# HDMI_RGB_LVDS_fertig_V3.net
KiCad netlist of a schematic drawn in EAGLE
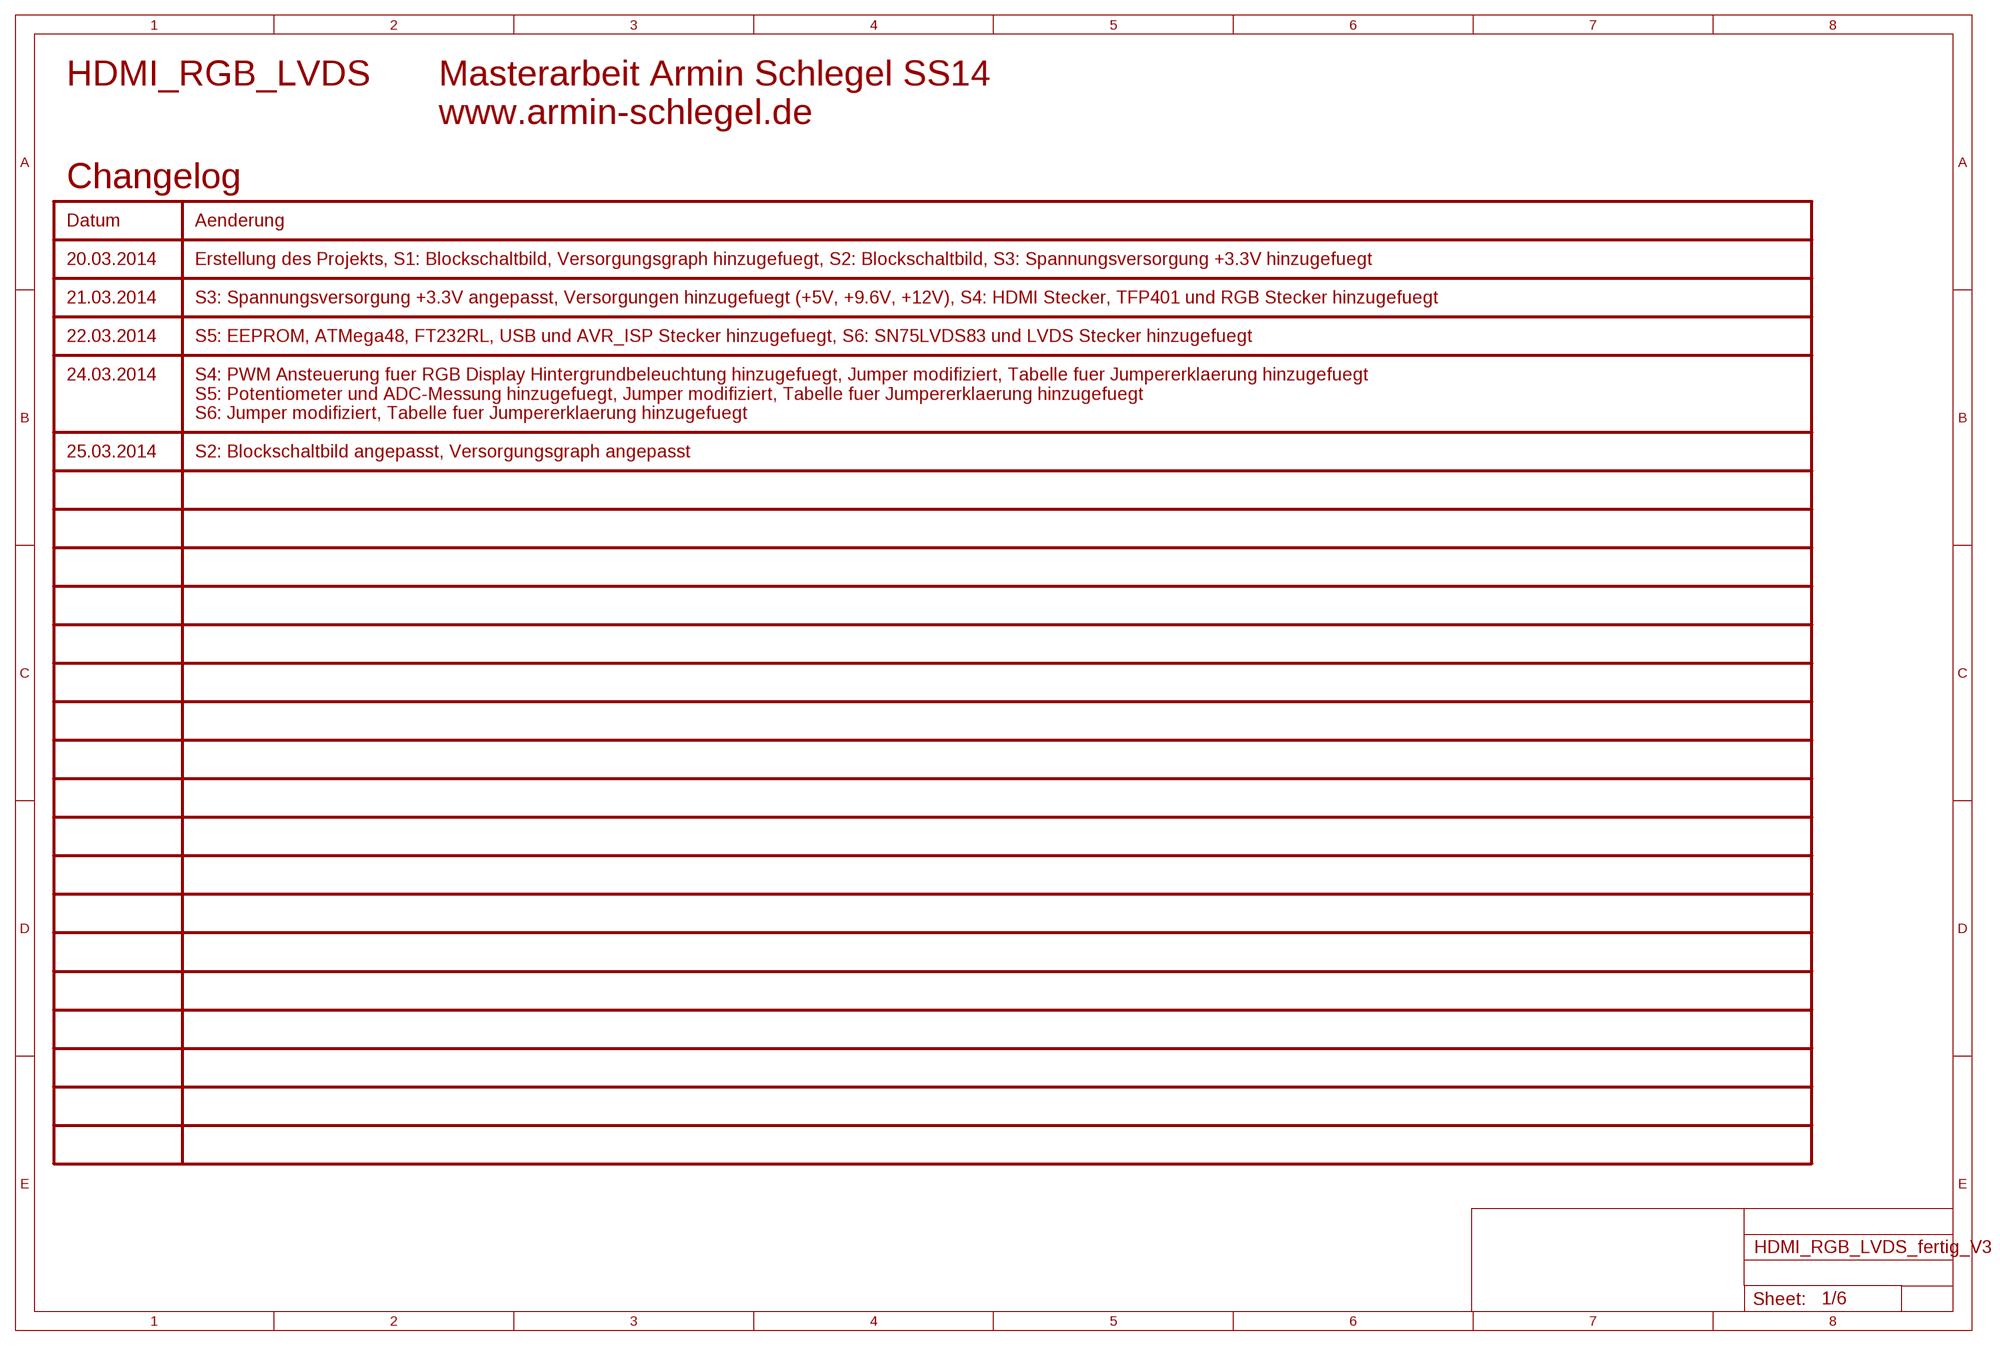
[diagram p0: schematic, sheet 1]
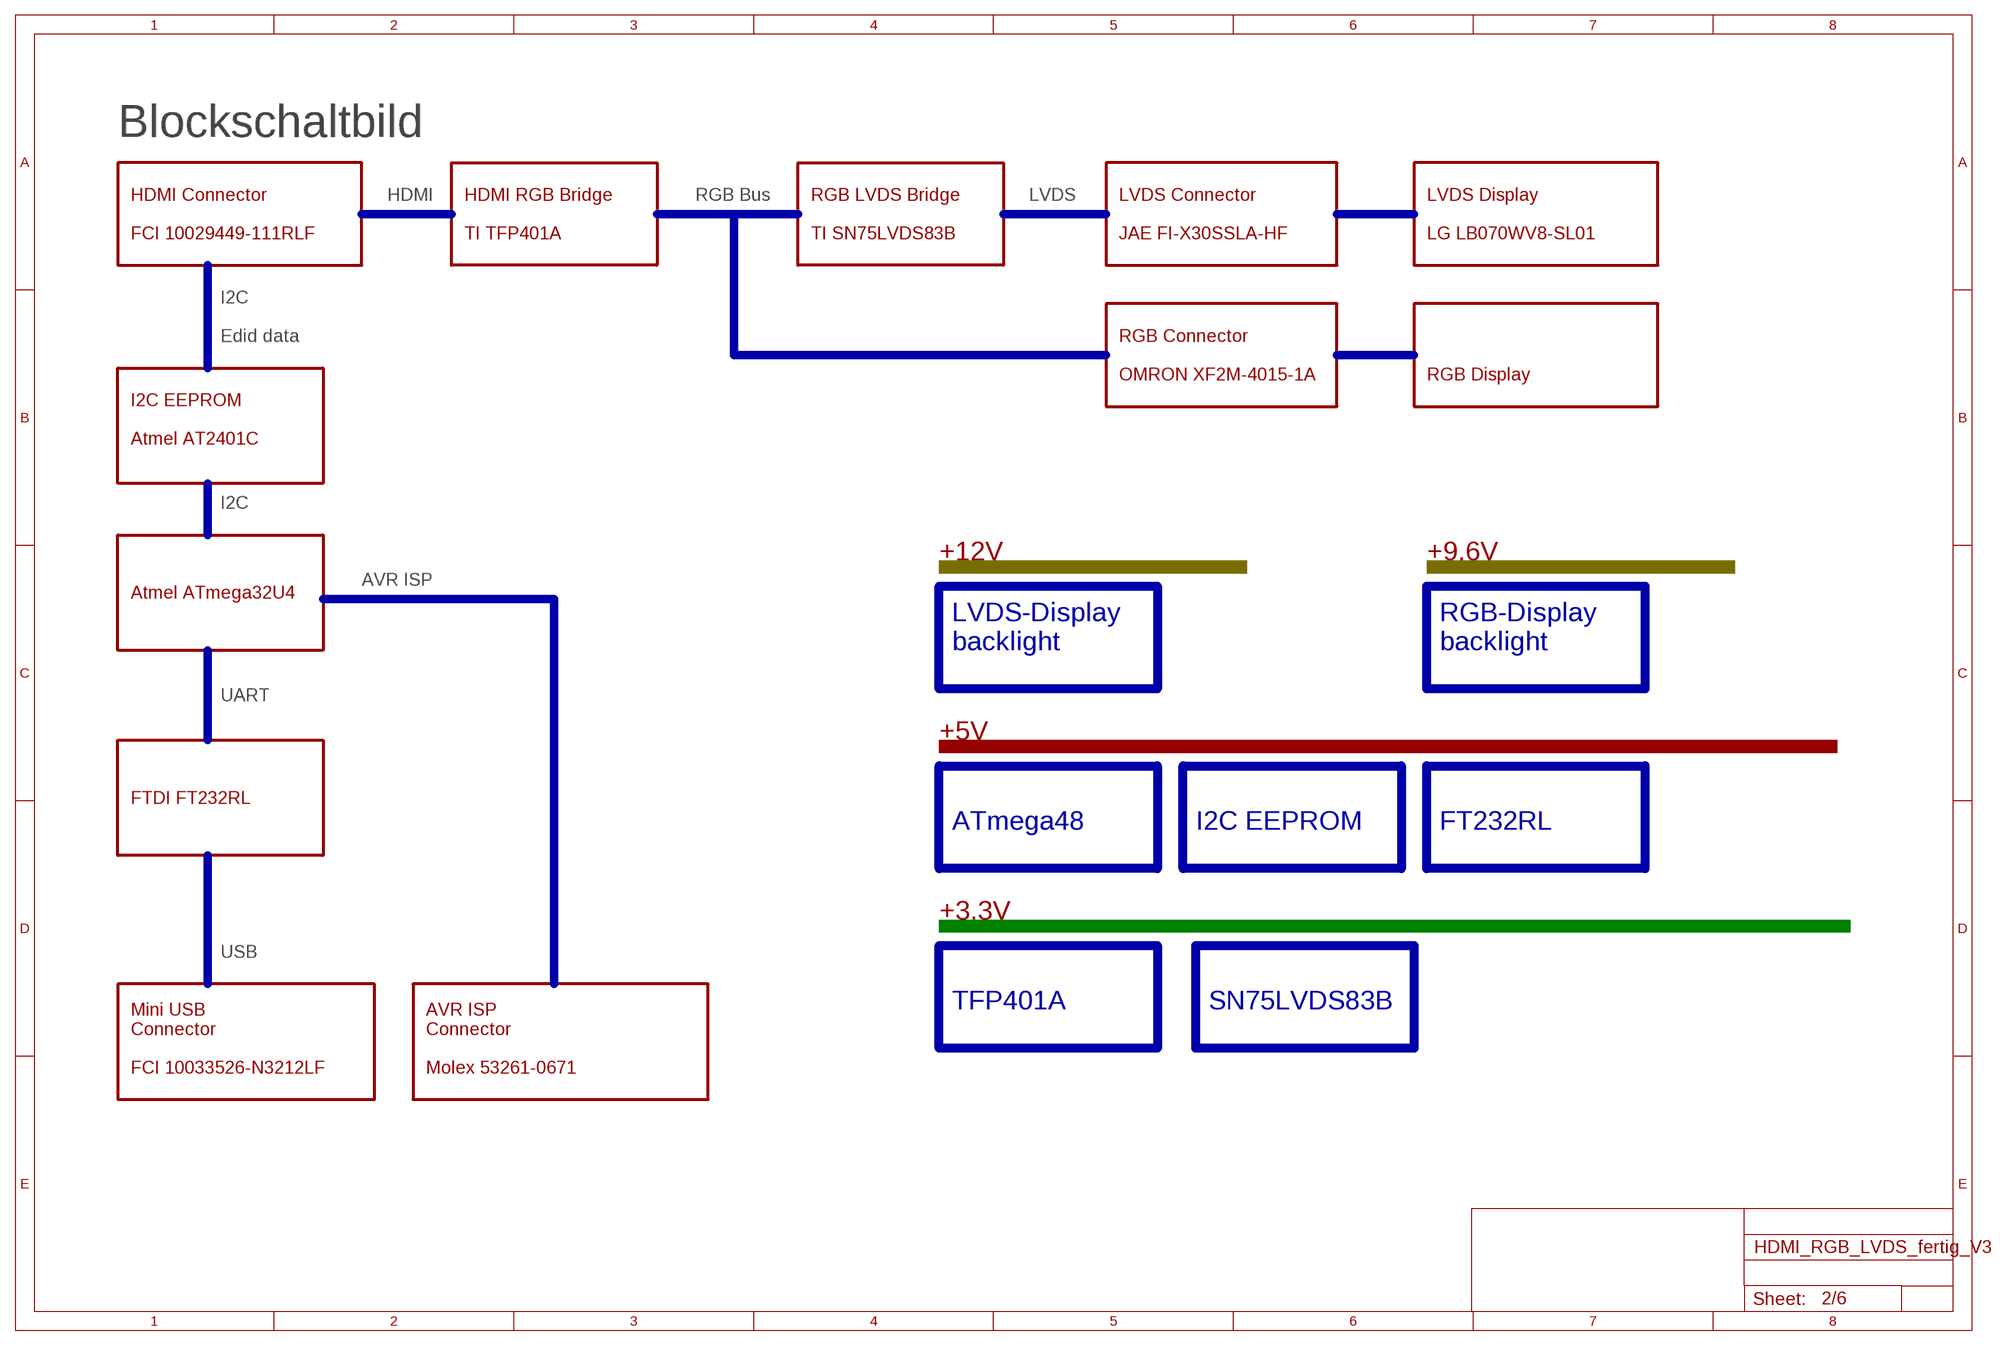
[diagram p1: schematic, sheet 2]
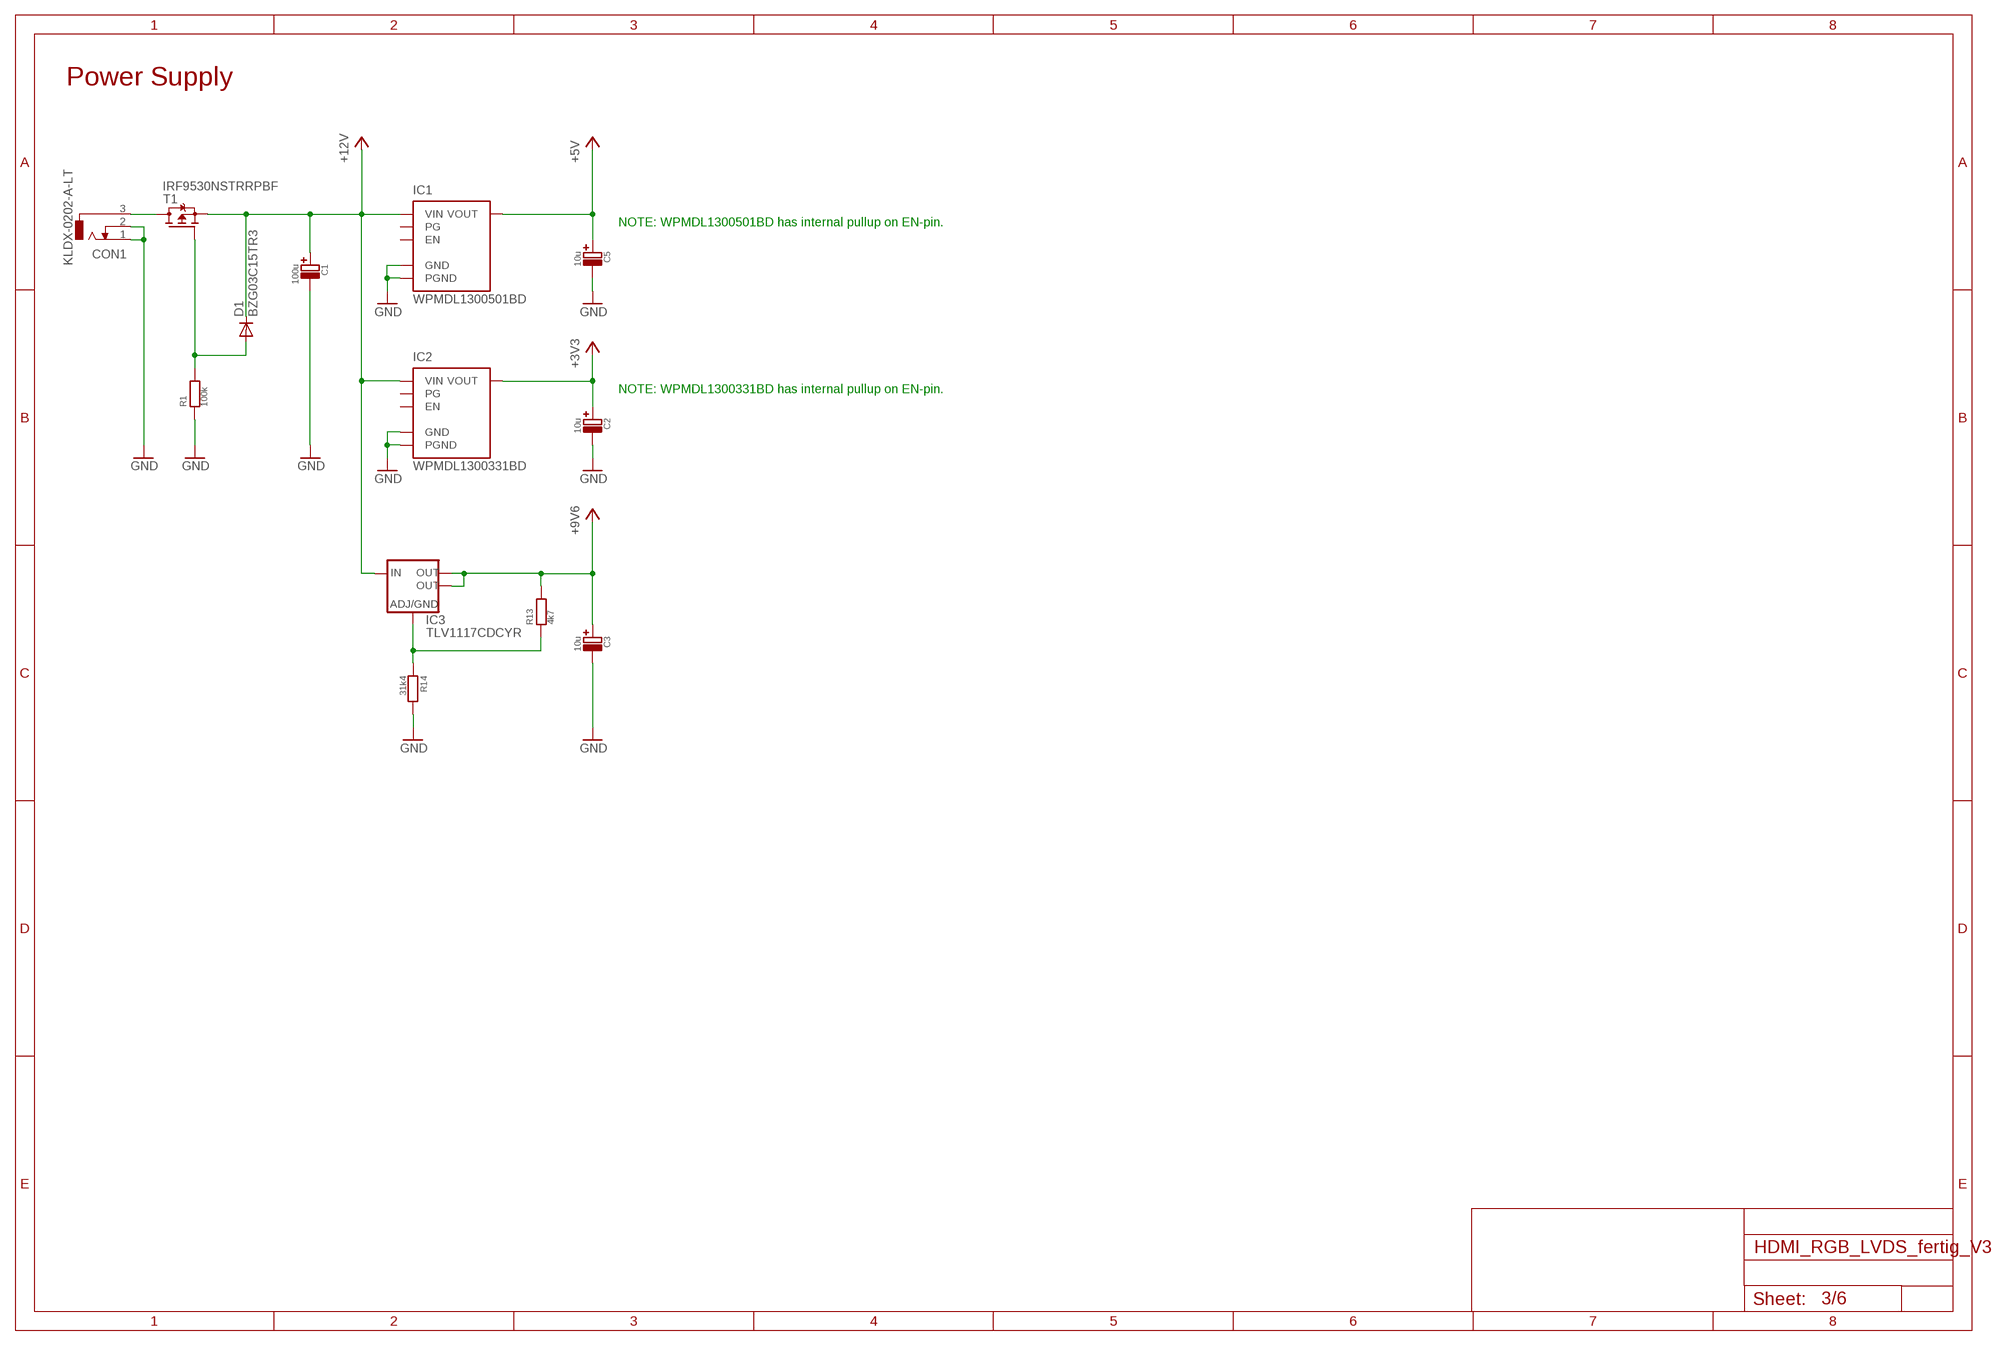
[diagram p2: schematic, sheet 3]
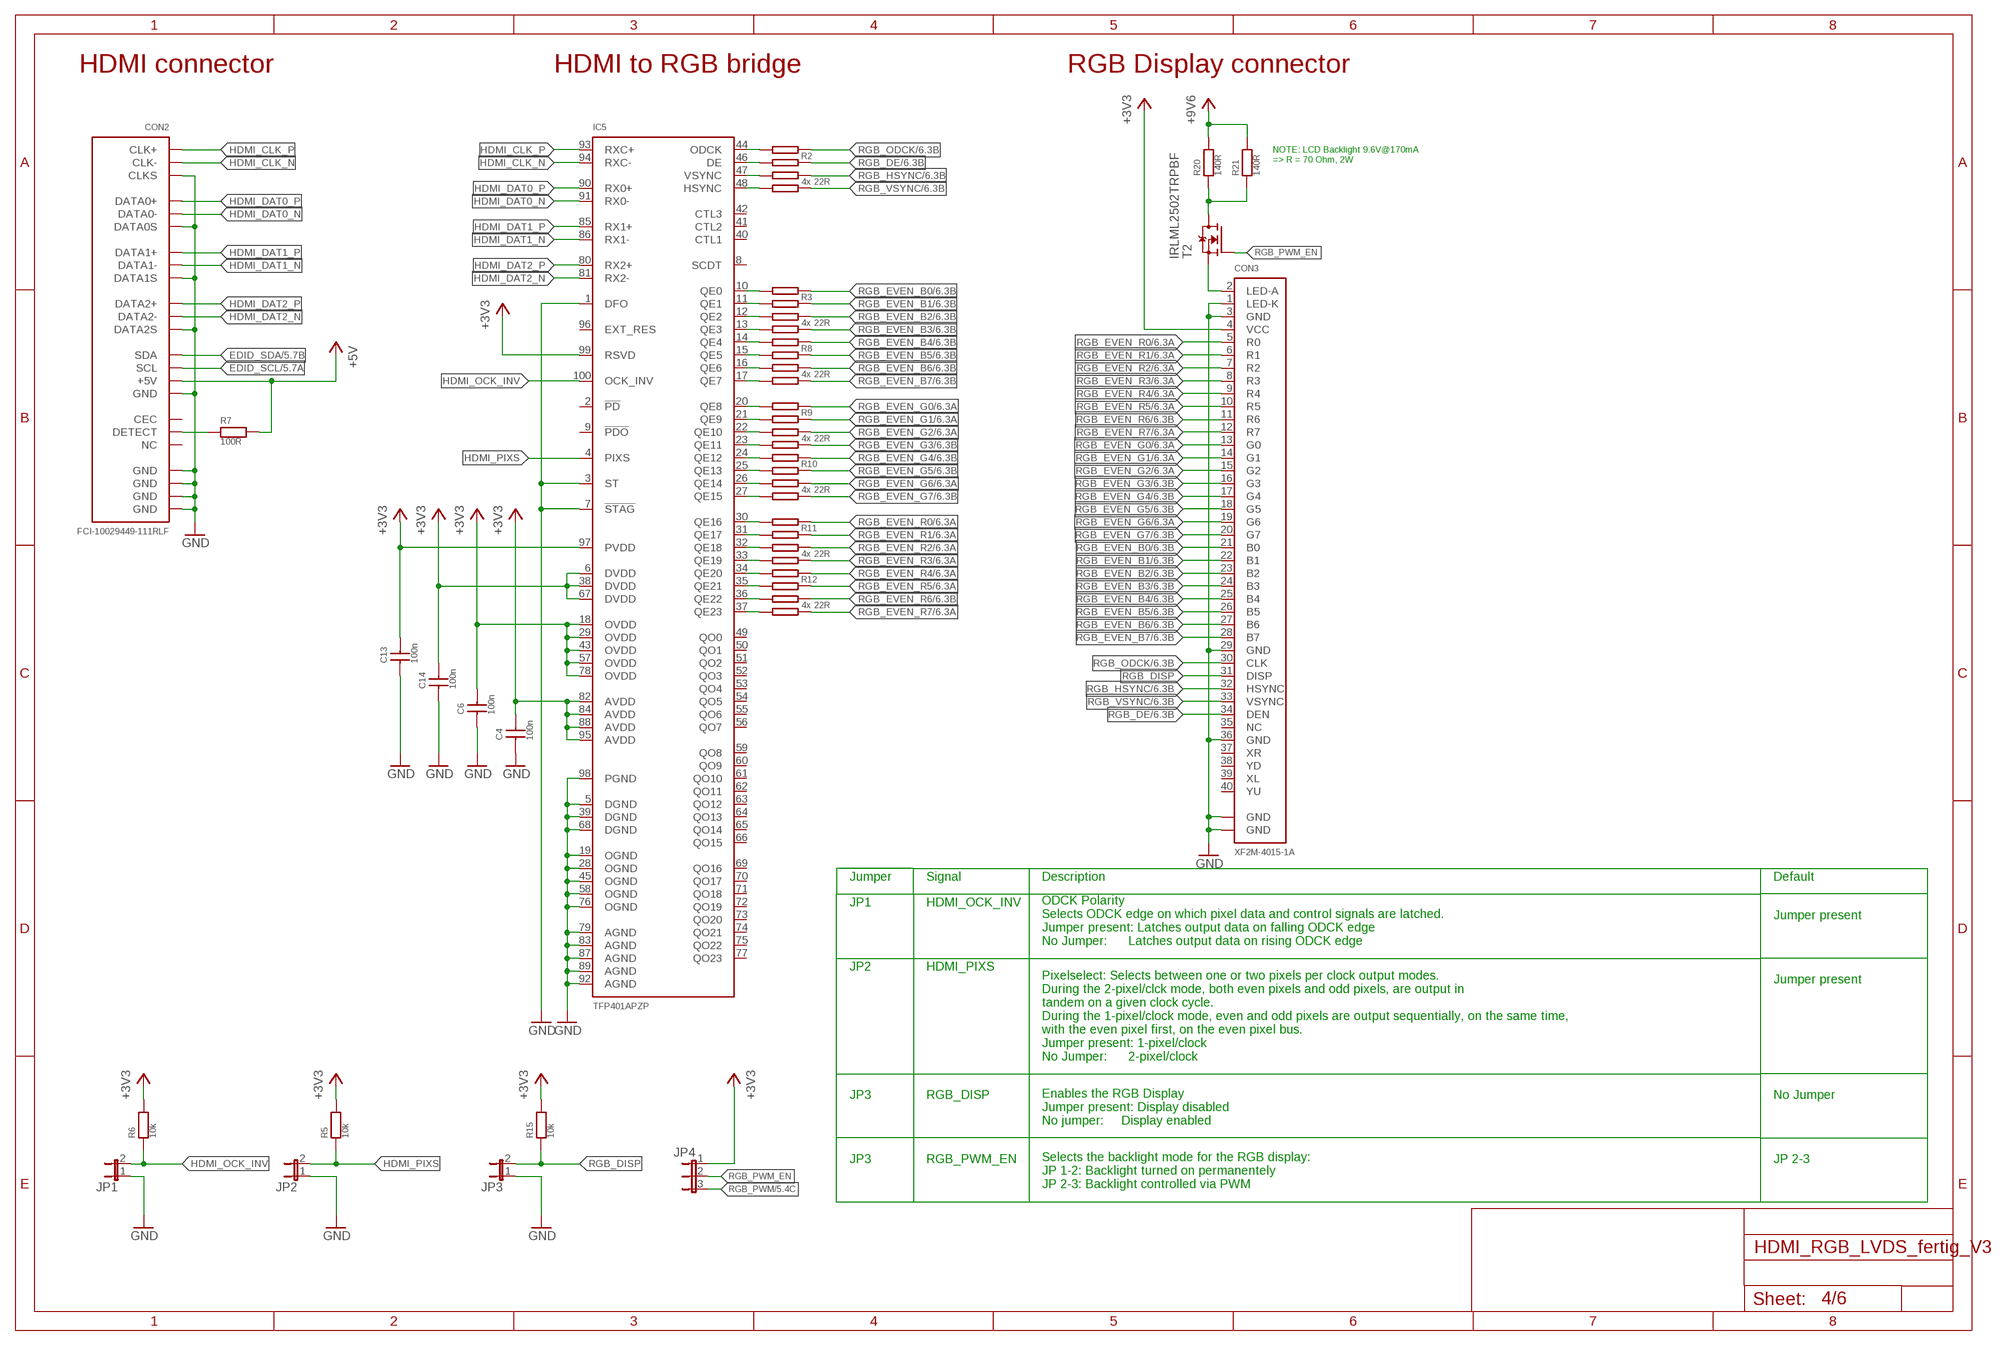
[diagram p3: schematic, sheet 4]
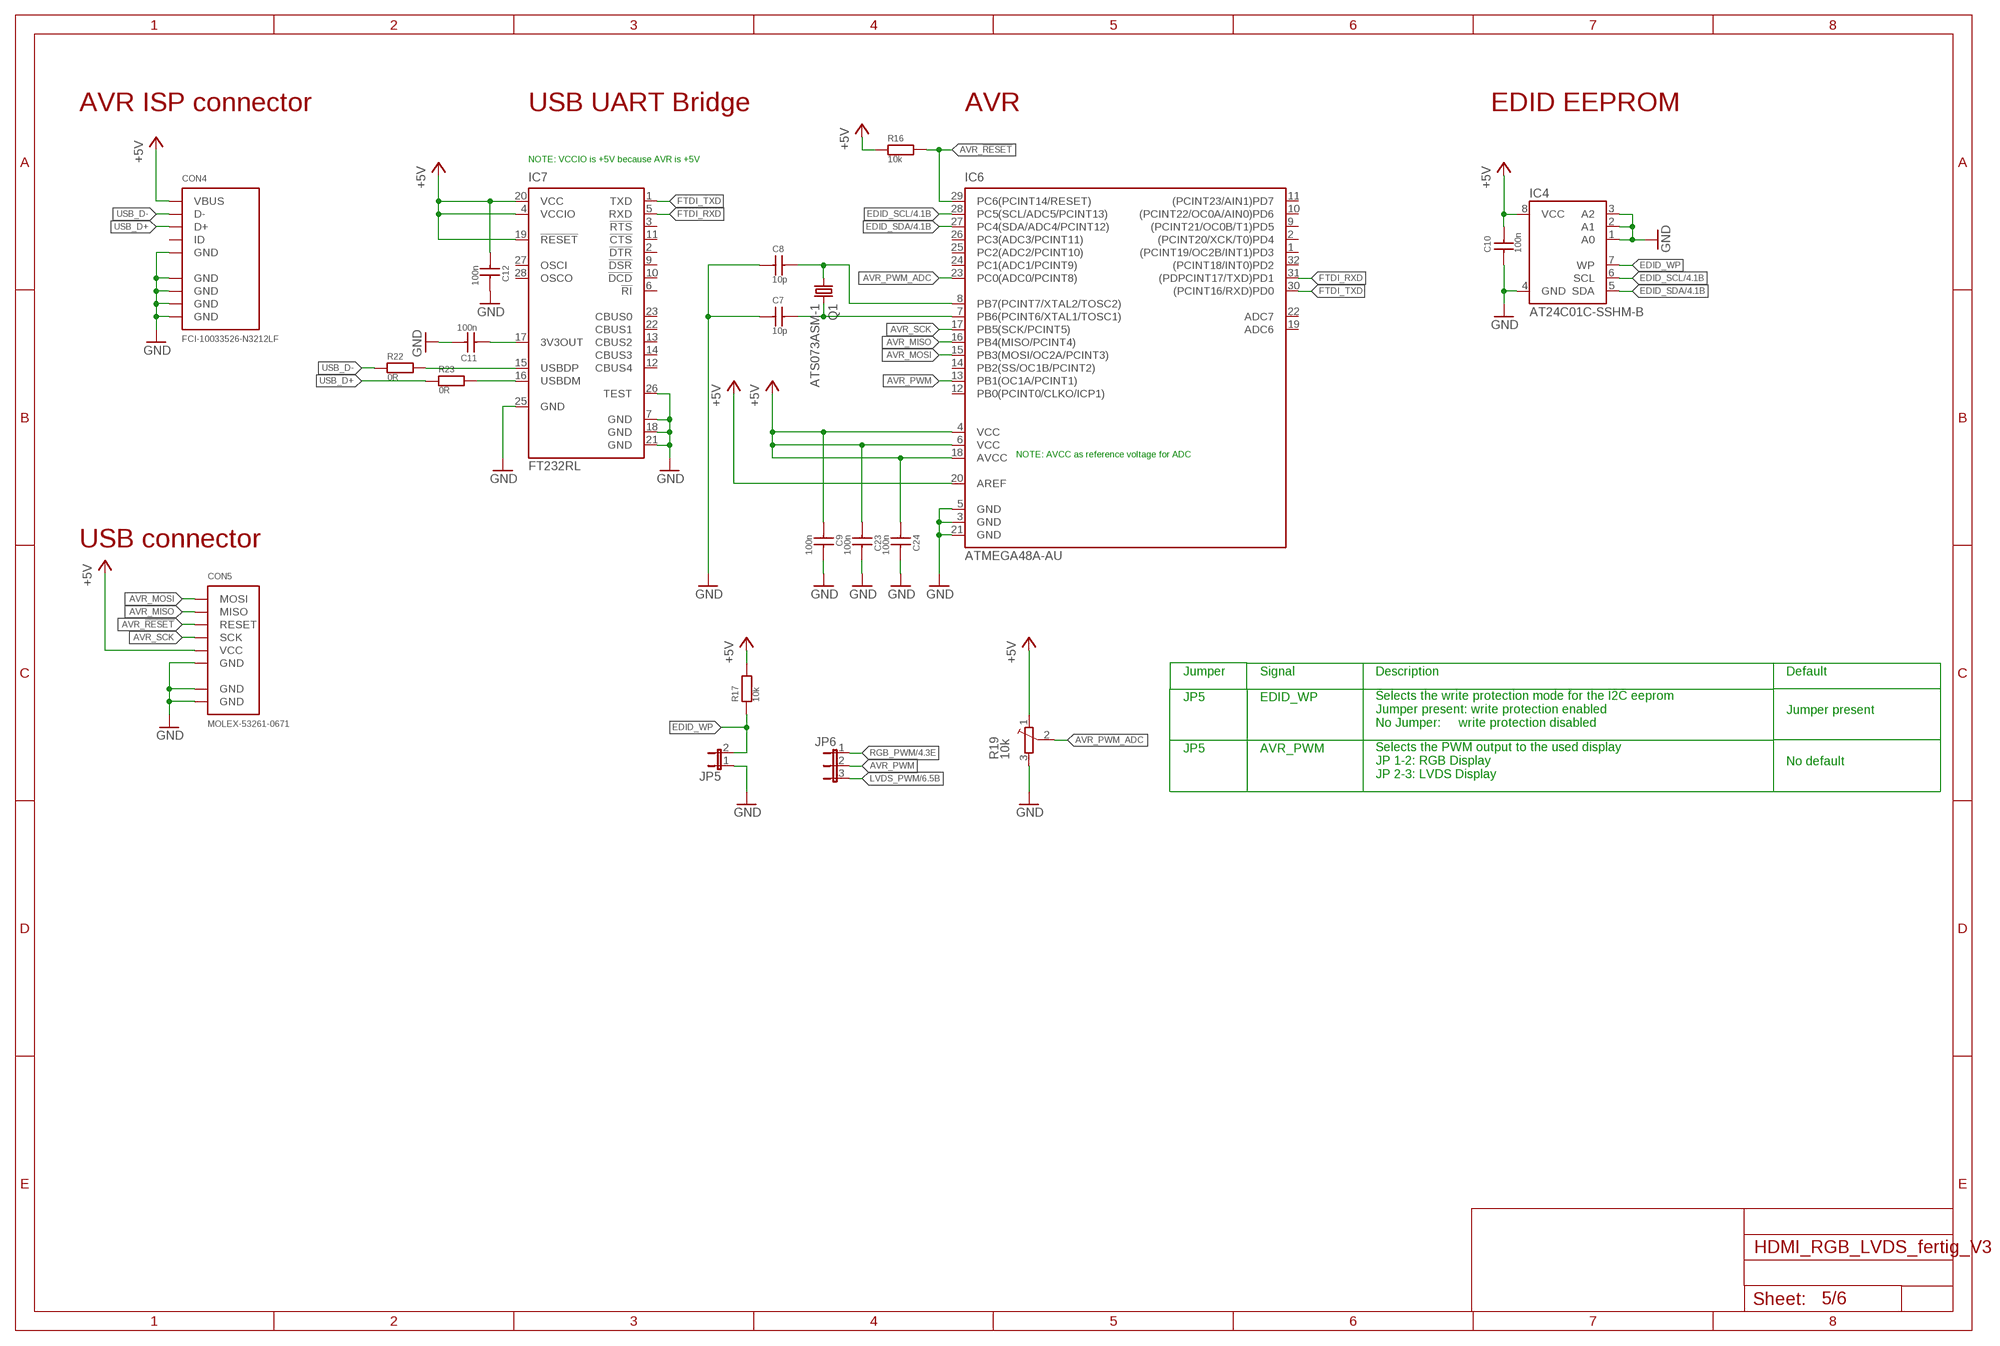
[diagram p4: schematic, sheet 5]
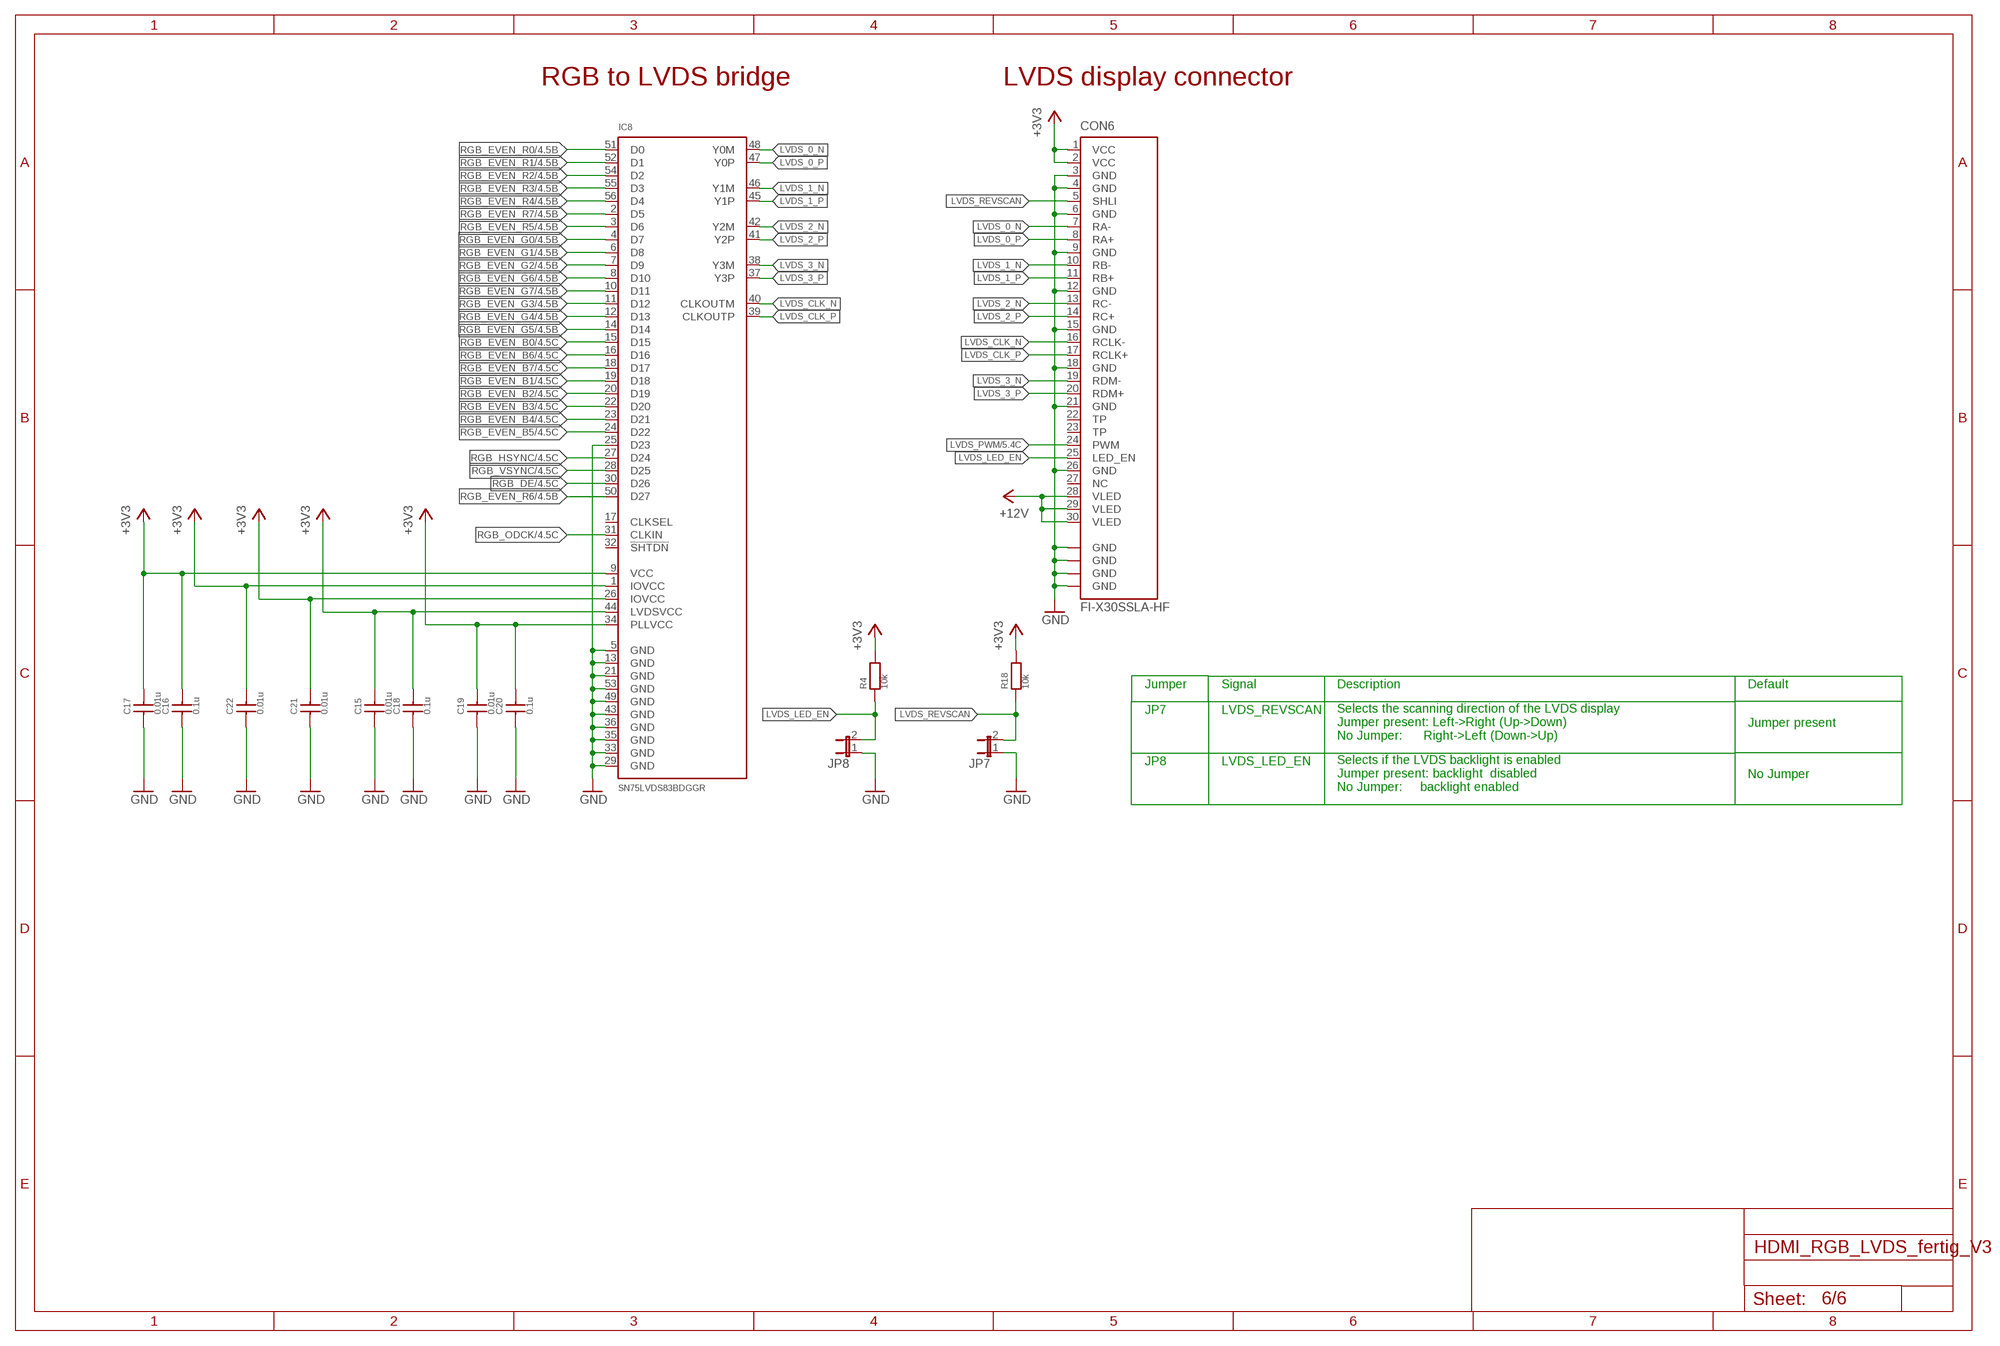
[diagram p5: schematic, sheet 6]

(export (version "E")
  (design (tool "Eeschema 10.0.6"))
  (components
    (comp (ref "C4")
      (value "100n")
      (footprint "eagle-import:C0402")
      (libsource (lib "eagle-import") (part "C_SMD0402"))
    )
    (comp (ref "C6")
      (value "100n")
      (footprint "eagle-import:C0402")
      (libsource (lib "eagle-import") (part "C_SMD0402"))
    )
    (comp (ref "C13")
      (value "100n")
      (footprint "eagle-import:C0402")
      (libsource (lib "eagle-import") (part "C_SMD0402"))
    )
    (comp (ref "C14")
      (value "100n")
      (footprint "eagle-import:C0402")
      (libsource (lib "eagle-import") (part "C_SMD0402"))
    )
    (comp (ref "CON2")
      (value "FCI-10029449-111RLF")
      (footprint "eagle-import:FCI-10029449-111RLF")
      (libsource (lib "eagle-import") (part "FCI-10029449-111RLF"))
    )
    (comp (ref "CON3")
      (value "XF2M-4015-1A")
      (footprint "eagle-import:XF2M-4015-1A")
      (libsource (lib "eagle-import") (part "XF2M-4015-1A"))
    )
    (comp (ref "IC5")
      (value "TFP401APZP")
      (footprint "eagle-import:HTQFP-100")
      (libsource (lib "eagle-import") (part "TFP401APZP"))
    )
    (comp (ref "JP1")
      (value "JUMPER2")
      (footprint "eagle-import:JUMPER2_THROUGHHOLE")
      (libsource (lib "eagle-import") (part "JUMPER2"))
    )
    (comp (ref "JP2")
      (value "JUMPER2")
      (footprint "eagle-import:JUMPER2_THROUGHHOLE")
      (libsource (lib "eagle-import") (part "JUMPER2"))
    )
    (comp (ref "JP3")
      (value "JUMPER2")
      (footprint "eagle-import:JUMPER2_THROUGHHOLE")
      (libsource (lib "eagle-import") (part "JUMPER2"))
    )
    (comp (ref "JP4")
      (value "JUMPER3")
      (footprint "eagle-import:JUMPER3_THROUGHHOLE")
      (libsource (lib "eagle-import") (part "JUMPER3"))
    )
    (comp (ref "R2")
      (value "22R")
      (footprint "eagle-import:R-ARRAY-4X0603")
      (libsource (lib "eagle-import") (part "CTR-742C083220JP-4X22R-4X0603"))
    )
    (comp (ref "R3")
      (value "22R")
      (footprint "eagle-import:R-ARRAY-4X0603")
      (libsource (lib "eagle-import") (part "CTR-742C083220JP-4X22R-4X0603"))
    )
    (comp (ref "R5")
      (value "10k")
      (footprint "eagle-import:R0402")
      (libsource (lib "eagle-import") (part "R0402"))
    )
    (comp (ref "R6")
      (value "10k")
      (footprint "eagle-import:R0402")
      (libsource (lib "eagle-import") (part "R0402"))
    )
    (comp (ref "R7")
      (value "100R")
      (footprint "eagle-import:R0402")
      (libsource (lib "eagle-import") (part "R0402"))
    )
    (comp (ref "R8")
      (value "22R")
      (footprint "eagle-import:R-ARRAY-4X0603")
      (libsource (lib "eagle-import") (part "CTR-742C083220JP-4X22R-4X0603"))
    )
    (comp (ref "R9")
      (value "22R")
      (footprint "eagle-import:R-ARRAY-4X0603")
      (libsource (lib "eagle-import") (part "CTR-742C083220JP-4X22R-4X0603"))
    )
    (comp (ref "R10")
      (value "22R")
      (footprint "eagle-import:R-ARRAY-4X0603")
      (libsource (lib "eagle-import") (part "CTR-742C083220JP-4X22R-4X0603"))
    )
    (comp (ref "R11")
      (value "22R")
      (footprint "eagle-import:R-ARRAY-4X0603")
      (libsource (lib "eagle-import") (part "CTR-742C083220JP-4X22R-4X0603"))
    )
    (comp (ref "R12")
      (value "22R")
      (footprint "eagle-import:R-ARRAY-4X0603")
      (libsource (lib "eagle-import") (part "CTR-742C083220JP-4X22R-4X0603"))
    )
    (comp (ref "R15")
      (value "10k")
      (footprint "eagle-import:R0402")
      (libsource (lib "eagle-import") (part "R0402"))
    )
    (comp (ref "R20")
      (value "140R")
      (footprint "eagle-import:R2512")
      (libsource (lib "eagle-import") (part "R2512"))
    )
    (comp (ref "R21")
      (value "140R")
      (footprint "eagle-import:R2512")
      (libsource (lib "eagle-import") (part "R2512"))
    )
    (comp (ref "T2")
      (value "IRLML2502TRPBF")
      (footprint "eagle-import:SOT23")
      (libsource (lib "eagle-import") (part "IRLML2502TRPBF"))
    )
    (comp (ref "U$3")
      (value "FRAME_A3_LANDSCAPE")
      (footprint "eagle-import:FRAME")
      (libsource (lib "eagle-import") (part "FRAME_A3_LANDSCAPE"))
    )
    (comp (ref "C15")
      (value "0.01u")
      (footprint "eagle-import:C0402")
      (libsource (lib "eagle-import") (part "C_SMD0402"))
    )
    (comp (ref "C16")
      (value "0.1u")
      (footprint "eagle-import:C0402")
      (libsource (lib "eagle-import") (part "C_SMD0402"))
    )
    (comp (ref "C17")
      (value "0.01u")
      (footprint "eagle-import:C0402")
      (libsource (lib "eagle-import") (part "C_SMD0402"))
    )
    (comp (ref "C18")
      (value "0.1u")
      (footprint "eagle-import:C0402")
      (libsource (lib "eagle-import") (part "C_SMD0402"))
    )
    (comp (ref "C19")
      (value "0.01u")
      (footprint "eagle-import:C0402")
      (libsource (lib "eagle-import") (part "C_SMD0402"))
    )
    (comp (ref "C20")
      (value "0.1u")
      (footprint "eagle-import:C0402")
      (libsource (lib "eagle-import") (part "C_SMD0402"))
    )
    (comp (ref "C21")
      (value "0.01u")
      (footprint "eagle-import:C0402")
      (libsource (lib "eagle-import") (part "C_SMD0402"))
    )
    (comp (ref "C22")
      (value "0.01u")
      (footprint "eagle-import:C0402")
      (libsource (lib "eagle-import") (part "C_SMD0402"))
    )
    (comp (ref "CON6")
      (value "FI-X30SSLA-HF")
      (footprint "eagle-import:FI-X30SSLA-HF")
      (libsource (lib "eagle-import") (part "FI-X30SSLA-HF"))
    )
    (comp (ref "IC8")
      (value "SN75LVDS83BDGGR")
      (footprint "eagle-import:TSSOP-56")
      (libsource (lib "eagle-import") (part "SN75LVDS83BDGGR"))
    )
    (comp (ref "JP7")
      (value "JUMPER2")
      (footprint "eagle-import:JUMPER2_THROUGHHOLE")
      (libsource (lib "eagle-import") (part "JUMPER2"))
    )
    (comp (ref "JP8")
      (value "JUMPER2")
      (footprint "eagle-import:JUMPER2_THROUGHHOLE")
      (libsource (lib "eagle-import") (part "JUMPER2"))
    )
    (comp (ref "R4")
      (value "10k")
      (footprint "eagle-import:R0402")
      (libsource (lib "eagle-import") (part "R0402"))
    )
    (comp (ref "R18")
      (value "10k")
      (footprint "eagle-import:R0402")
      (libsource (lib "eagle-import") (part "R0402"))
    )
    (comp (ref "U$5")
      (value "FRAME_A3_LANDSCAPE")
      (footprint "eagle-import:FRAME")
      (libsource (lib "eagle-import") (part "FRAME_A3_LANDSCAPE"))
    )
    (comp (ref "U$15")
      (value "FRAME_A3_LANDSCAPE")
      (footprint "eagle-import:FRAME")
      (libsource (lib "eagle-import") (part "FRAME_A3_LANDSCAPE"))
    )
    (comp (ref "C1")
      (value "100u")
      (footprint "eagle-import:C_POL_6X6MM")
      (libsource (lib "eagle-import") (part "C_POL6X6MM"))
    )
    (comp (ref "C2")
      (value "10u")
      (footprint "eagle-import:C_POL_4X4MM")
      (libsource (lib "eagle-import") (part "C_POL4X4MM"))
    )
    (comp (ref "C3")
      (value "10u")
      (footprint "eagle-import:C_POL_4X4MM")
      (libsource (lib "eagle-import") (part "C_POL4X4MM"))
    )
    (comp (ref "C5")
      (value "10u")
      (footprint "eagle-import:C_POL_4X4MM")
      (libsource (lib "eagle-import") (part "C_POL4X4MM"))
    )
    (comp (ref "CON1")
      (value "KLDX-0202-A-LT")
      (footprint "eagle-import:KLDX-0202-A-LT")
      (libsource (lib "eagle-import") (part "KLDX-0202-A-LT"))
    )
    (comp (ref "D1")
      (value "BZG03C15TR3")
      (footprint "eagle-import:DO214A")
      (libsource (lib "eagle-import") (part "BZG03C15TR3"))
    )
    (comp (ref "IC1")
      (value "WPMDL1300501BD")
      (footprint "eagle-import:TO263-5")
      (libsource (lib "eagle-import") (part "WPMDL1300501BD"))
    )
    (comp (ref "IC2")
      (value "WPMDL1300331BD")
      (footprint "eagle-import:TO263-5")
      (libsource (lib "eagle-import") (part "WPMDL1300331BD"))
    )
    (comp (ref "IC3")
      (value "TLV1117CDCYR")
      (footprint "eagle-import:SOT223")
      (libsource (lib "eagle-import") (part "TLV1117CDCYR"))
    )
    (comp (ref "R1")
      (value "100k")
      (footprint "eagle-import:R0402")
      (libsource (lib "eagle-import") (part "R0402"))
    )
    (comp (ref "R13")
      (value "4k7")
      (footprint "eagle-import:R0402")
      (libsource (lib "eagle-import") (part "R0402"))
    )
    (comp (ref "R14")
      (value "31k4")
      (footprint "eagle-import:R0402")
      (libsource (lib "eagle-import") (part "R0402"))
    )
    (comp (ref "T1")
      (value "IRF9530NSTRRPBF")
      (footprint "eagle-import:D2PAK")
      (libsource (lib "eagle-import") (part "IRF9530NSTRRPBF"))
    )
    (comp (ref "U$2")
      (value "FRAME_A3_LANDSCAPE")
      (footprint "eagle-import:FRAME")
      (libsource (lib "eagle-import") (part "FRAME_A3_LANDSCAPE"))
    )
    (comp (ref "C7")
      (value "10p")
      (footprint "eagle-import:C0402")
      (libsource (lib "eagle-import") (part "C_SMD0402"))
    )
    (comp (ref "C8")
      (value "10p")
      (footprint "eagle-import:C0402")
      (libsource (lib "eagle-import") (part "C_SMD0402"))
    )
    (comp (ref "C9")
      (value "100n")
      (footprint "eagle-import:C0402")
      (libsource (lib "eagle-import") (part "C_SMD0402"))
    )
    (comp (ref "C10")
      (value "100n")
      (footprint "eagle-import:C0402")
      (libsource (lib "eagle-import") (part "C_SMD0402"))
    )
    (comp (ref "C11")
      (value "100n")
      (footprint "eagle-import:C0402")
      (libsource (lib "eagle-import") (part "C_SMD0402"))
    )
    (comp (ref "C12")
      (value "100n")
      (footprint "eagle-import:C0402")
      (libsource (lib "eagle-import") (part "C_SMD0402"))
    )
    (comp (ref "C23")
      (value "100n")
      (footprint "eagle-import:C0402")
      (libsource (lib "eagle-import") (part "C_SMD0402"))
    )
    (comp (ref "C24")
      (value "100n")
      (footprint "eagle-import:C0402")
      (libsource (lib "eagle-import") (part "C_SMD0402"))
    )
    (comp (ref "CON4")
      (value "FCI-10033526-N3212LF")
      (footprint "eagle-import:FCI-10033526-N3212LF")
      (libsource (lib "eagle-import") (part "FCI-10033526-N3212LF"))
    )
    (comp (ref "CON5")
      (value "MOLEX-53261-0671")
      (footprint "eagle-import:MOLEX-53261-0671")
      (libsource (lib "eagle-import") (part "MOLEX-53261-0671"))
    )
    (comp (ref "IC4")
      (value "AT24C01C-SSHM-B")
      (footprint "eagle-import:SOIC8")
      (libsource (lib "eagle-import") (part "AT24C01C-SSHM-B"))
    )
    (comp (ref "IC6")
      (value "ATMEGA48A-AU")
      (footprint "eagle-import:TQFP32")
      (libsource (lib "eagle-import") (part "ATMEGA48A-AU"))
    )
    (comp (ref "IC7")
      (value "FT232RL")
      (footprint "eagle-import:SSOP28")
      (libsource (lib "eagle-import") (part "FT232RL"))
    )
    (comp (ref "JP5")
      (value "JUMPER2")
      (footprint "eagle-import:JUMPER2_THROUGHHOLE")
      (libsource (lib "eagle-import") (part "JUMPER2"))
    )
    (comp (ref "JP6")
      (value "JUMPER3")
      (footprint "eagle-import:JUMPER3_THROUGHHOLE")
      (libsource (lib "eagle-import") (part "JUMPER3"))
    )
    (comp (ref "Q1")
      (value "ATS073ASM-1")
      (footprint "eagle-import:HC49_USSM")
      (libsource (lib "eagle-import") (part "ATS073ASM-1"))
    )
    (comp (ref "R16")
      (value "10k")
      (footprint "eagle-import:R0402")
      (libsource (lib "eagle-import") (part "R0402"))
    )
    (comp (ref "R17")
      (value "10k")
      (footprint "eagle-import:R0402")
      (libsource (lib "eagle-import") (part "R0402"))
    )
    (comp (ref "R19")
      (value "10k")
      (footprint "eagle-import:35WR5KLFTR")
      (libsource (lib "eagle-import") (part "35WR5KLFTR"))
    )
    (comp (ref "R22")
      (value "0R")
      (footprint "eagle-import:R0402")
      (libsource (lib "eagle-import") (part "R0402"))
    )
    (comp (ref "R23")
      (value "0R")
      (footprint "eagle-import:R0402")
      (libsource (lib "eagle-import") (part "R0402"))
    )
    (comp (ref "U$4")
      (value "FRAME_A3_LANDSCAPE")
      (footprint "eagle-import:FRAME")
      (libsource (lib "eagle-import") (part "FRAME_A3_LANDSCAPE"))
    )
    (comp (ref "U$1")
      (value "FRAME_A3_LANDSCAPE")
      (footprint "eagle-import:FRAME")
      (libsource (lib "eagle-import") (part "FRAME_A3_LANDSCAPE"))
    )
  )
  (nets
    (net (code "3") (name "+3V3") (class "Default")
      (node (ref "C13") (pin "2") (pinfunction "P$2_2") (pintype "passive"))
      (node (ref "C14") (pin "2") (pinfunction "P$2_2") (pintype "passive"))
      (node (ref "C15") (pin "2") (pinfunction "P$2_2") (pintype "passive"))
      (node (ref "C16") (pin "2") (pinfunction "P$2_2") (pintype "passive"))
      (node (ref "C17") (pin "2") (pinfunction "P$2_2") (pintype "passive"))
      (node (ref "C18") (pin "2") (pinfunction "P$2_2") (pintype "passive"))
      (node (ref "C19") (pin "2") (pinfunction "P$2_2") (pintype "passive"))
      (node (ref "C2") (pin "+") (pinfunction "P$1_+") (pintype "passive"))
      (node (ref "C20") (pin "2") (pinfunction "P$2_2") (pintype "passive"))
      (node (ref "C21") (pin "2") (pinfunction "P$2_2") (pintype "passive"))
      (node (ref "C22") (pin "2") (pinfunction "P$2_2") (pintype "passive"))
      (node (ref "C4") (pin "2") (pinfunction "P$2_2") (pintype "passive"))
      (node (ref "C6") (pin "2") (pinfunction "P$2_2") (pintype "passive"))
      (node (ref "CON3") (pin "4") (pinfunction "VCC_4") (pintype "bidirectional"))
      (node (ref "CON6") (pin "1") (pinfunction "VCC_1") (pintype "bidirectional"))
      (node (ref "CON6") (pin "2") (pinfunction "VCC_2") (pintype "bidirectional"))
      (node (ref "IC2") (pin "3") (pinfunction "VOUT_3") (pintype "bidirectional"))
      (node (ref "IC5") (pin "18") (pinfunction "OVDD_18") (pintype "power_in"))
      (node (ref "IC5") (pin "29") (pinfunction "OVDD_29") (pintype "power_in"))
      (node (ref "IC5") (pin "38") (pinfunction "DVDD_38") (pintype "power_in"))
      (node (ref "IC5") (pin "43") (pinfunction "OVDD_43") (pintype "power_in"))
      (node (ref "IC5") (pin "57") (pinfunction "OVDD_57") (pintype "power_in"))
      (node (ref "IC5") (pin "6") (pinfunction "DVDD_6") (pintype "power_in"))
      (node (ref "IC5") (pin "67") (pinfunction "DVDD_67") (pintype "power_in"))
      (node (ref "IC5") (pin "78") (pinfunction "OVDD_78") (pintype "power_in"))
      (node (ref "IC5") (pin "82") (pinfunction "AVDD_82") (pintype "power_in"))
      (node (ref "IC5") (pin "84") (pinfunction "AVDD_84") (pintype "power_in"))
      (node (ref "IC5") (pin "88") (pinfunction "AVDD_88") (pintype "power_in"))
      (node (ref "IC5") (pin "95") (pinfunction "AVDD_95") (pintype "power_in"))
      (node (ref "IC5") (pin "97") (pinfunction "PVDD_97") (pintype "power_in"))
      (node (ref "IC5") (pin "99") (pinfunction "RSVD_99") (pintype "bidirectional"))
      (node (ref "IC8") (pin "1") (pinfunction "IOVCC_1") (pintype "power_in"))
      (node (ref "IC8") (pin "26") (pinfunction "IOVCC_26") (pintype "power_in"))
      (node (ref "IC8") (pin "34") (pinfunction "PLLVCC_34") (pintype "power_in"))
      (node (ref "IC8") (pin "44") (pinfunction "LVDSVCC_44") (pintype "power_in"))
      (node (ref "IC8") (pin "9") (pinfunction "VCC_9") (pintype "power_in"))
      (node (ref "JP4") (pin "1") (pinfunction "1_1") (pintype "passive"))
      (node (ref "R15") (pin "2") (pinfunction "P$2_2") (pintype "passive"))
      (node (ref "R18") (pin "2") (pinfunction "P$2_2") (pintype "passive"))
      (node (ref "R4") (pin "2") (pinfunction "P$2_2") (pintype "passive"))
      (node (ref "R5") (pin "2") (pinfunction "P$2_2") (pintype "passive"))
      (node (ref "R6") (pin "2") (pinfunction "P$2_2") (pintype "passive"))
    )
    (net (code "4") (name "+5V") (class "Default")
      (node (ref "C10") (pin "2") (pinfunction "P$2_2") (pintype "passive"))
      (node (ref "C12") (pin "1") (pinfunction "P$1_1") (pintype "passive"))
      (node (ref "C23") (pin "1") (pinfunction "P$1_1") (pintype "passive"))
      (node (ref "C24") (pin "1") (pinfunction "P$1_1") (pintype "passive"))
      (node (ref "C5") (pin "+") (pinfunction "P$1_+") (pintype "passive"))
      (node (ref "C9") (pin "1") (pinfunction "P$1_1") (pintype "passive"))
      (node (ref "CON2") (pin "18") (pinfunction "+5V_18") (pintype "bidirectional"))
      (node (ref "CON4") (pin "1") (pinfunction "VBUS_1") (pintype "bidirectional"))
      (node (ref "CON5") (pin "5") (pinfunction "VCC_5") (pintype "bidirectional"))
      (node (ref "IC1") (pin "3") (pinfunction "VOUT_3") (pintype "bidirectional"))
      (node (ref "IC4") (pin "8") (pinfunction "VCC_8") (pintype "power_in"))
      (node (ref "IC6") (pin "18") (pinfunction "AVCC_18") (pintype "power_in"))
      (node (ref "IC6") (pin "20") (pinfunction "AREF_20") (pintype "power_in"))
      (node (ref "IC6") (pin "4") (pinfunction "VCC_4") (pintype "power_in"))
      (node (ref "IC6") (pin "6") (pinfunction "VCC_6") (pintype "power_in"))
      (node (ref "IC7") (pin "19") (pinfunction "~{RESET}_19") (pintype "input"))
      (node (ref "IC7") (pin "20") (pinfunction "VCC_20") (pintype "power_in"))
      (node (ref "IC7") (pin "4") (pinfunction "VCCIO_4") (pintype "power_in"))
      (node (ref "R16") (pin "1") (pinfunction "P$1_1") (pintype "passive"))
      (node (ref "R17") (pin "2") (pinfunction "P$2_2") (pintype "passive"))
      (node (ref "R19") (pin "1") (pinfunction "E_1") (pintype "passive"))
      (node (ref "R7") (pin "2") (pinfunction "P$2_2") (pintype "passive"))
    )
    (net (code "5") (name "+9V6") (class "Default")
      (node (ref "C3") (pin "+") (pinfunction "P$1_+") (pintype "passive"))
      (node (ref "IC3") (pin "2") (pinfunction "OUT_2") (pintype "passive"))
      (node (ref "IC3") (pin "4") (pinfunction "OUT1_4") (pintype "passive"))
      (node (ref "R13") (pin "2") (pinfunction "P$2_2") (pintype "passive"))
      (node (ref "R20") (pin "2") (pinfunction "P$2_2") (pintype "passive"))
      (node (ref "R21") (pin "2") (pinfunction "P$2_2") (pintype "passive"))
    )
    (net (code "6") (name "+12V") (class "Default")
      (node (ref "C1") (pin "+") (pinfunction "P$1_+") (pintype "passive"))
      (node (ref "CON6") (pin "28") (pinfunction "VLED_28") (pintype "bidirectional"))
      (node (ref "CON6") (pin "29") (pinfunction "VLED_29") (pintype "bidirectional"))
      (node (ref "CON6") (pin "30") (pinfunction "VLED_30") (pintype "bidirectional"))
      (node (ref "D1") (pin "C") (pinfunction "C_C") (pintype "passive"))
      (node (ref "IC1") (pin "1") (pinfunction "VIN_1") (pintype "bidirectional"))
      (node (ref "IC2") (pin "1") (pinfunction "VIN_1") (pintype "bidirectional"))
      (node (ref "IC3") (pin "3") (pinfunction "IN_3") (pintype "input"))
      (node (ref "T1") (pin "3") (pinfunction "S_3") (pintype "passive"))
    )
    (net (code "9") (name "AVR_MISO") (class "Default")
      (node (ref "CON5") (pin "2") (pinfunction "MISO_2") (pintype "bidirectional"))
      (node (ref "IC6") (pin "16") (pinfunction "PB4(MISO/PCINT4)_16") (pintype "bidirectional"))
    )
    (net (code "10") (name "AVR_MOSI") (class "Default")
      (node (ref "CON5") (pin "1") (pinfunction "MOSI_1") (pintype "bidirectional"))
      (node (ref "IC6") (pin "15") (pinfunction "PB3(MOSI/OC2A/PCINT3)_15") (pintype "bidirectional"))
    )
    (net (code "11") (name "AVR_PWM") (class "Default")
      (node (ref "IC6") (pin "13") (pinfunction "PB1(OC1A/PCINT1)_13") (pintype "bidirectional"))
      (node (ref "JP6") (pin "2") (pinfunction "2_2") (pintype "passive"))
    )
    (net (code "12") (name "AVR_PWM_ADC") (class "Default")
      (node (ref "IC6") (pin "23") (pinfunction "PC0(ADC0/PCINT8)_23") (pintype "bidirectional"))
      (node (ref "R19") (pin "2") (pinfunction "S_2") (pintype "passive"))
    )
    (net (code "13") (name "AVR_SCK") (class "Default")
      (node (ref "CON5") (pin "4") (pinfunction "SCK_4") (pintype "bidirectional"))
      (node (ref "IC6") (pin "17") (pinfunction "PB5(SCK/PCINT5)_17") (pintype "bidirectional"))
    )
    (net (code "14") (name "AVR_~{RESET}") (class "Default")
      (node (ref "CON5") (pin "3") (pinfunction "RESET_3") (pintype "bidirectional"))
      (node (ref "IC6") (pin "29") (pinfunction "PC6(PCINT14/RESET)_29") (pintype "bidirectional"))
      (node (ref "R16") (pin "2") (pinfunction "P$2_2") (pintype "passive"))
    )
    (net (code "15") (name "EDID_SCL") (class "Default")
      (node (ref "CON2") (pin "15") (pinfunction "SCL_15") (pintype "bidirectional"))
      (node (ref "IC4") (pin "6") (pinfunction "SCL_6") (pintype "bidirectional"))
      (node (ref "IC6") (pin "28") (pinfunction "PC5(SCL/ADC5/PCINT13)_28") (pintype "bidirectional"))
    )
    (net (code "16") (name "EDID_SDA") (class "Default")
      (node (ref "CON2") (pin "16") (pinfunction "SDA_16") (pintype "bidirectional"))
      (node (ref "IC4") (pin "5") (pinfunction "SDA_5") (pintype "bidirectional"))
      (node (ref "IC6") (pin "27") (pinfunction "PC4(SDA/ADC4/PCINT12)_27") (pintype "bidirectional"))
    )
    (net (code "17") (name "EDID_WP") (class "Default")
      (node (ref "IC4") (pin "7") (pinfunction "WP_7") (pintype "input"))
      (node (ref "JP5") (pin "2") (pinfunction "2_2") (pintype "passive"))
      (node (ref "R17") (pin "1") (pinfunction "P$1_1") (pintype "passive"))
    )
    (net (code "18") (name "FTDI_RXD") (class "Default")
      (node (ref "IC6") (pin "31") (pinfunction "(PDPCINT17/TXD)PD1_31") (pintype "bidirectional"))
      (node (ref "IC7") (pin "5") (pinfunction "RXD_5") (pintype "input"))
    )
    (net (code "19") (name "FTDI_TXD") (class "Default")
      (node (ref "IC6") (pin "30") (pinfunction "(PCINT16/RXD)PD0_30") (pintype "bidirectional"))
      (node (ref "IC7") (pin "1") (pinfunction "TXD_1") (pintype "output"))
    )
    (net (code "20") (name "GND") (class "Default")
      (node (ref "C1") (pin "-") (pinfunction "P$2_-") (pintype "passive"))
      (node (ref "C10") (pin "1") (pinfunction "P$1_1") (pintype "passive"))
      (node (ref "C11") (pin "2") (pinfunction "P$2_2") (pintype "passive"))
      (node (ref "C12") (pin "2") (pinfunction "P$2_2") (pintype "passive"))
      (node (ref "C13") (pin "1") (pinfunction "P$1_1") (pintype "passive"))
      (node (ref "C14") (pin "1") (pinfunction "P$1_1") (pintype "passive"))
      (node (ref "C15") (pin "1") (pinfunction "P$1_1") (pintype "passive"))
      (node (ref "C16") (pin "1") (pinfunction "P$1_1") (pintype "passive"))
      (node (ref "C17") (pin "1") (pinfunction "P$1_1") (pintype "passive"))
      (node (ref "C18") (pin "1") (pinfunction "P$1_1") (pintype "passive"))
      (node (ref "C19") (pin "1") (pinfunction "P$1_1") (pintype "passive"))
      (node (ref "C2") (pin "-") (pinfunction "P$2_-") (pintype "passive"))
      (node (ref "C20") (pin "1") (pinfunction "P$1_1") (pintype "passive"))
      (node (ref "C21") (pin "1") (pinfunction "P$1_1") (pintype "passive"))
      (node (ref "C22") (pin "1") (pinfunction "P$1_1") (pintype "passive"))
      (node (ref "C23") (pin "2") (pinfunction "P$2_2") (pintype "passive"))
      (node (ref "C24") (pin "2") (pinfunction "P$2_2") (pintype "passive"))
      (node (ref "C3") (pin "-") (pinfunction "P$2_-") (pintype "passive"))
      (node (ref "C4") (pin "1") (pinfunction "P$1_1") (pintype "passive"))
      (node (ref "C5") (pin "-") (pinfunction "P$2_-") (pintype "passive"))
      (node (ref "C6") (pin "1") (pinfunction "P$1_1") (pintype "passive"))
      (node (ref "C7") (pin "1") (pinfunction "P$1_1") (pintype "passive"))
      (node (ref "C8") (pin "1") (pinfunction "P$1_1") (pintype "passive"))
      (node (ref "C9") (pin "2") (pinfunction "P$2_2") (pintype "passive"))
      (node (ref "CON1") (pin "1") (pinfunction "3_1") (pintype "passive"))
      (node (ref "CON1") (pin "2") (pinfunction "2_2") (pintype "passive"))
      (node (ref "CON2") (pin "11") (pinfunction "CLKS_11") (pintype "bidirectional"))
      (node (ref "CON2") (pin "17") (pinfunction "GND_17") (pintype "bidirectional"))
      (node (ref "CON2") (pin "2") (pinfunction "DATA2S_2") (pintype "bidirectional"))
      (node (ref "CON2") (pin "5") (pinfunction "DATA1S_5") (pintype "bidirectional"))
      (node (ref "CON2") (pin "8") (pinfunction "DATA0S_8") (pintype "bidirectional"))
      (node (ref "CON2") (pin "GND@1") (pinfunction "GND_GND@1") (pintype "power_in"))
      (node (ref "CON2") (pin "GND@2") (pinfunction "GND_GND@2") (pintype "power_in"))
      (node (ref "CON2") (pin "GND@3") (pinfunction "GND_GND@3") (pintype "power_in"))
      (node (ref "CON2") (pin "GND@4") (pinfunction "GND_GND@4") (pintype "power_in"))
      (node (ref "CON3") (pin "1") (pinfunction "LED-K_1") (pintype "bidirectional"))
      (node (ref "CON3") (pin "29") (pinfunction "GND_29") (pintype "bidirectional"))
      (node (ref "CON3") (pin "3") (pinfunction "GND_3") (pintype "bidirectional"))
      (node (ref "CON3") (pin "36") (pinfunction "GND_36") (pintype "bidirectional"))
      (node (ref "CON3") (pin "GND@1") (pinfunction "GND_GND@1") (pintype "power_in"))
      (node (ref "CON3") (pin "GND@2") (pinfunction "GND_GND@2") (pintype "power_in"))
      (node (ref "CON4") (pin "5") (pinfunction "GND_5") (pintype "bidirectional"))
      (node (ref "CON4") (pin "GND@1") (pinfunction "GND_GND@1") (pintype "power_in"))
      (node (ref "CON4") (pin "GND@2") (pinfunction "GND_GND@2") (pintype "power_in"))
      (node (ref "CON4") (pin "GND@3") (pinfunction "GND_GND@3") (pintype "power_in"))
      (node (ref "CON4") (pin "GND@4") (pinfunction "GND_GND@4") (pintype "power_in"))
      (node (ref "CON5") (pin "6") (pinfunction "GND_6") (pintype "bidirectional"))
      (node (ref "CON5") (pin "GND@1") (pinfunction "GND_GND@1") (pintype "power_in"))
      (node (ref "CON5") (pin "GND@2") (pinfunction "GND_GND@2") (pintype "power_in"))
      (node (ref "CON6") (pin "12") (pinfunction "GND_12") (pintype "bidirectional"))
      (node (ref "CON6") (pin "15") (pinfunction "GND_15") (pintype "bidirectional"))
      (node (ref "CON6") (pin "18") (pinfunction "GND_18") (pintype "bidirectional"))
      (node (ref "CON6") (pin "21") (pinfunction "GND_21") (pintype "bidirectional"))
      (node (ref "CON6") (pin "26") (pinfunction "GND_26") (pintype "bidirectional"))
      (node (ref "CON6") (pin "3") (pinfunction "GND_3") (pintype "bidirectional"))
      (node (ref "CON6") (pin "4") (pinfunction "GND_4") (pintype "bidirectional"))
      (node (ref "CON6") (pin "6") (pinfunction "GND_6") (pintype "bidirectional"))
      (node (ref "CON6") (pin "9") (pinfunction "GND_9") (pintype "bidirectional"))
      (node (ref "CON6") (pin "GND@1") (pinfunction "GND_GND@1") (pintype "power_in"))
      (node (ref "CON6") (pin "GND@2") (pinfunction "GND_GND@2") (pintype "power_in"))
      (node (ref "CON6") (pin "GND@3") (pinfunction "GND_GND@3") (pintype "power_in"))
      (node (ref "CON6") (pin "GND@4") (pinfunction "GND_GND@4") (pintype "power_in"))
      (node (ref "IC1") (pin "2") (pinfunction "GND_2") (pintype "bidirectional"))
      (node (ref "IC1") (pin "6") (pinfunction "PGND_6") (pintype "bidirectional"))
      (node (ref "IC2") (pin "2") (pinfunction "GND_2") (pintype "bidirectional"))
      (node (ref "IC2") (pin "6") (pinfunction "PGND_6") (pintype "bidirectional"))
      (node (ref "IC4") (pin "1") (pinfunction "A0_1") (pintype "input"))
      (node (ref "IC4") (pin "2") (pinfunction "A1_2") (pintype "input"))
      (node (ref "IC4") (pin "3") (pinfunction "A2_3") (pintype "input"))
      (node (ref "IC4") (pin "4") (pinfunction "GND_4") (pintype "power_in"))
      (node (ref "IC5") (pin "1") (pinfunction "DFO_1") (pintype "bidirectional"))
      (node (ref "IC5") (pin "19") (pinfunction "OGND_19") (pintype "power_in"))
      (node (ref "IC5") (pin "28") (pinfunction "OGND_28") (pintype "power_in"))
      (node (ref "IC5") (pin "3") (pinfunction "ST_3") (pintype "bidirectional"))
      (node (ref "IC5") (pin "39") (pinfunction "DGND_39") (pintype "power_in"))
      (node (ref "IC5") (pin "45") (pinfunction "OGND_45") (pintype "power_in"))
      (node (ref "IC5") (pin "5") (pinfunction "DGND_5") (pintype "power_in"))
      (node (ref "IC5") (pin "58") (pinfunction "OGND_58") (pintype "power_in"))
      (node (ref "IC5") (pin "68") (pinfunction "DGND_68") (pintype "power_in"))
      (node (ref "IC5") (pin "7") (pinfunction "~{STAG}_7") (pintype "bidirectional"))
      (node (ref "IC5") (pin "76") (pinfunction "OGND_76") (pintype "power_in"))
      (node (ref "IC5") (pin "79") (pinfunction "AGND_79") (pintype "power_in"))
      (node (ref "IC5") (pin "83") (pinfunction "AGND_83") (pintype "power_in"))
      (node (ref "IC5") (pin "87") (pinfunction "AGND_87") (pintype "power_in"))
      (node (ref "IC5") (pin "89") (pinfunction "AGND_89") (pintype "power_in"))
      (node (ref "IC5") (pin "92") (pinfunction "AGND_92") (pintype "power_in"))
      (node (ref "IC5") (pin "98") (pinfunction "PGND_98") (pintype "power_in"))
      (node (ref "IC6") (pin "21") (pinfunction "GND_21") (pintype "power_in"))
      (node (ref "IC6") (pin "3") (pinfunction "GND_3") (pintype "power_in"))
      (node (ref "IC6") (pin "5") (pinfunction "GND_5") (pintype "power_in"))
      (node (ref "IC7") (pin "18") (pinfunction "GND_18") (pintype "power_in"))
      (node (ref "IC7") (pin "21") (pinfunction "GND_21") (pintype "power_in"))
      (node (ref "IC7") (pin "25") (pinfunction "GND_25") (pintype "power_in"))
      (node (ref "IC7") (pin "26") (pinfunction "TEST_26") (pintype "input"))
      (node (ref "IC7") (pin "7") (pinfunction "GND_7") (pintype "power_in"))
      (node (ref "IC8") (pin "13") (pinfunction "GND_13") (pintype "power_in"))
      (node (ref "IC8") (pin "21") (pinfunction "GND_21") (pintype "power_in"))
      (node (ref "IC8") (pin "25") (pinfunction "D23_25") (pintype "bidirectional"))
      (node (ref "IC8") (pin "29") (pinfunction "GND_29") (pintype "power_in"))
      (node (ref "IC8") (pin "33") (pinfunction "GND_33") (pintype "power_in"))
      (node (ref "IC8") (pin "35") (pinfunction "GND_35") (pintype "power_in"))
      (node (ref "IC8") (pin "36") (pinfunction "GND_36") (pintype "power_in"))
      (node (ref "IC8") (pin "43") (pinfunction "GND_43") (pintype "power_in"))
      (node (ref "IC8") (pin "49") (pinfunction "GND_49") (pintype "power_in"))
      (node (ref "IC8") (pin "5") (pinfunction "GND_5") (pintype "power_in"))
      (node (ref "IC8") (pin "53") (pinfunction "GND_53") (pintype "power_in"))
      (node (ref "JP1") (pin "1") (pinfunction "1_1") (pintype "passive"))
      (node (ref "JP2") (pin "1") (pinfunction "1_1") (pintype "passive"))
      (node (ref "JP3") (pin "1") (pinfunction "1_1") (pintype "passive"))
      (node (ref "JP5") (pin "1") (pinfunction "1_1") (pintype "passive"))
      (node (ref "JP7") (pin "1") (pinfunction "1_1") (pintype "passive"))
      (node (ref "JP8") (pin "1") (pinfunction "1_1") (pintype "passive"))
      (node (ref "R1") (pin "1") (pinfunction "P$1_1") (pintype "passive"))
      (node (ref "R14") (pin "2") (pinfunction "P$2_2") (pintype "passive"))
      (node (ref "R19") (pin "3") (pinfunction "A_3") (pintype "passive"))
    )
    (net (code "21") (name "HDMI_CLK_N") (class "Default")
      (node (ref "CON2") (pin "12") (pinfunction "CLK-_12") (pintype "bidirectional"))
      (node (ref "IC5") (pin "94") (pinfunction "RXC-_94") (pintype "bidirectional"))
    )
    (net (code "22") (name "HDMI_CLK_P") (class "Default")
      (node (ref "CON2") (pin "10") (pinfunction "CLK+_10") (pintype "bidirectional"))
      (node (ref "IC5") (pin "93") (pinfunction "RXC+_93") (pintype "bidirectional"))
    )
    (net (code "23") (name "HDMI_DAT0_N") (class "Default")
      (node (ref "CON2") (pin "9") (pinfunction "DATA0-_9") (pintype "bidirectional"))
      (node (ref "IC5") (pin "91") (pinfunction "RX0-_91") (pintype "bidirectional"))
    )
    (net (code "24") (name "HDMI_DAT0_P") (class "Default")
      (node (ref "CON2") (pin "7") (pinfunction "DATA0+_7") (pintype "bidirectional"))
      (node (ref "IC5") (pin "90") (pinfunction "RX0+_90") (pintype "bidirectional"))
    )
    (net (code "25") (name "HDMI_DAT1_N") (class "Default")
      (node (ref "CON2") (pin "6") (pinfunction "DATA1-_6") (pintype "bidirectional"))
      (node (ref "IC5") (pin "86") (pinfunction "RX1-_86") (pintype "bidirectional"))
    )
    (net (code "26") (name "HDMI_DAT1_P") (class "Default")
      (node (ref "CON2") (pin "4") (pinfunction "DATA1+_4") (pintype "bidirectional"))
      (node (ref "IC5") (pin "85") (pinfunction "RX1+_85") (pintype "bidirectional"))
    )
    (net (code "27") (name "HDMI_DAT2_N") (class "Default")
      (node (ref "CON2") (pin "3") (pinfunction "DATA2-_3") (pintype "bidirectional"))
      (node (ref "IC5") (pin "81") (pinfunction "RX2-_81") (pintype "bidirectional"))
    )
    (net (code "28") (name "HDMI_DAT2_P") (class "Default")
      (node (ref "CON2") (pin "1") (pinfunction "DATA2+_1") (pintype "bidirectional"))
      (node (ref "IC5") (pin "80") (pinfunction "RX2+_80") (pintype "bidirectional"))
    )
    (net (code "29") (name "HDMI_OCK_INV") (class "Default")
      (node (ref "IC5") (pin "100") (pinfunction "OCK_INV_100") (pintype "bidirectional"))
      (node (ref "JP1") (pin "2") (pinfunction "2_2") (pintype "passive"))
      (node (ref "R6") (pin "1") (pinfunction "P$1_1") (pintype "passive"))
    )
    (net (code "30") (name "HDMI_PIXS") (class "Default")
      (node (ref "IC5") (pin "4") (pinfunction "PIXS_4") (pintype "bidirectional"))
      (node (ref "JP2") (pin "2") (pinfunction "2_2") (pintype "passive"))
      (node (ref "R5") (pin "1") (pinfunction "P$1_1") (pintype "passive"))
    )
    (net (code "31") (name "LVDS_0_N") (class "Default")
      (node (ref "CON6") (pin "7") (pinfunction "RA-_7") (pintype "bidirectional"))
      (node (ref "IC8") (pin "48") (pinfunction "Y0M_48") (pintype "bidirectional"))
    )
    (net (code "32") (name "LVDS_0_P") (class "Default")
      (node (ref "CON6") (pin "8") (pinfunction "RA+_8") (pintype "bidirectional"))
      (node (ref "IC8") (pin "47") (pinfunction "Y0P_47") (pintype "bidirectional"))
    )
    (net (code "33") (name "LVDS_1_N") (class "Default")
      (node (ref "CON6") (pin "10") (pinfunction "RB-_10") (pintype "bidirectional"))
      (node (ref "IC8") (pin "46") (pinfunction "Y1M_46") (pintype "bidirectional"))
    )
    (net (code "34") (name "LVDS_1_P") (class "Default")
      (node (ref "CON6") (pin "11") (pinfunction "RB+_11") (pintype "bidirectional"))
      (node (ref "IC8") (pin "45") (pinfunction "Y1P_45") (pintype "bidirectional"))
    )
    (net (code "35") (name "LVDS_2_N") (class "Default")
      (node (ref "CON6") (pin "13") (pinfunction "RC-_13") (pintype "bidirectional"))
      (node (ref "IC8") (pin "42") (pinfunction "Y2M_42") (pintype "bidirectional"))
    )
    (net (code "36") (name "LVDS_2_P") (class "Default")
      (node (ref "CON6") (pin "14") (pinfunction "RC+_14") (pintype "bidirectional"))
      (node (ref "IC8") (pin "41") (pinfunction "Y2P_41") (pintype "bidirectional"))
    )
    (net (code "37") (name "LVDS_3_N") (class "Default")
      (node (ref "CON6") (pin "19") (pinfunction "RDM-_19") (pintype "bidirectional"))
      (node (ref "IC8") (pin "38") (pinfunction "Y3M_38") (pintype "bidirectional"))
    )
    (net (code "38") (name "LVDS_3_P") (class "Default")
      (node (ref "CON6") (pin "20") (pinfunction "RDM+_20") (pintype "bidirectional"))
      (node (ref "IC8") (pin "37") (pinfunction "Y3P_37") (pintype "bidirectional"))
    )
    (net (code "39") (name "LVDS_CLK_N") (class "Default")
      (node (ref "CON6") (pin "16") (pinfunction "RCLK-_16") (pintype "bidirectional"))
      (node (ref "IC8") (pin "40") (pinfunction "CLKOUTM_40") (pintype "bidirectional"))
    )
    (net (code "40") (name "LVDS_CLK_P") (class "Default")
      (node (ref "CON6") (pin "17") (pinfunction "RCLK+_17") (pintype "bidirectional"))
      (node (ref "IC8") (pin "39") (pinfunction "CLKOUTP_39") (pintype "bidirectional"))
    )
    (net (code "41") (name "LVDS_LED_EN") (class "Default")
      (node (ref "CON6") (pin "25") (pinfunction "LED_EN_25") (pintype "bidirectional"))
      (node (ref "JP8") (pin "2") (pinfunction "2_2") (pintype "passive"))
      (node (ref "R4") (pin "1") (pinfunction "P$1_1") (pintype "passive"))
    )
    (net (code "42") (name "LVDS_PWM") (class "Default")
      (node (ref "CON6") (pin "24") (pinfunction "PWM_24") (pintype "bidirectional"))
      (node (ref "JP6") (pin "3") (pinfunction "3_3") (pintype "passive"))
    )
    (net (code "43") (name "LVDS_REVSCAN") (class "Default")
      (node (ref "CON6") (pin "5") (pinfunction "SHLI_5") (pintype "bidirectional"))
      (node (ref "JP7") (pin "2") (pinfunction "2_2") (pintype "passive"))
      (node (ref "R18") (pin "1") (pinfunction "P$1_1") (pintype "passive"))
    )
    (net (code "44") (name "Net-(C7-P$2)") (class "Default")
      (node (ref "C7") (pin "2") (pinfunction "P$2_2") (pintype "passive"))
      (node (ref "IC6") (pin "7") (pinfunction "PB6(PCINT6/XTAL1/TOSC1)_7") (pintype "bidirectional"))
      (node (ref "Q1") (pin "2") (pinfunction "2_2") (pintype "passive"))
    )
    (net (code "45") (name "Net-(C8-P$2)") (class "Default")
      (node (ref "C8") (pin "2") (pinfunction "P$2_2") (pintype "passive"))
      (node (ref "IC6") (pin "8") (pinfunction "PB7(PCINT7/XTAL2/TOSC2)_8") (pintype "bidirectional"))
      (node (ref "Q1") (pin "1") (pinfunction "1_1") (pintype "passive"))
    )
    (net (code "46") (name "Net-(C11-P$1)") (class "Default")
      (node (ref "C11") (pin "1") (pinfunction "P$1_1") (pintype "passive"))
      (node (ref "IC7") (pin "17") (pinfunction "3V3OUT_17") (pintype "output"))
    )
    (net (code "47") (name "Net-(CON1-1)") (class "Default")
      (node (ref "CON1") (pin "3") (pinfunction "1_3") (pintype "passive"))
      (node (ref "T1") (pin "2") (pinfunction "D_2") (pintype "passive"))
    )
    (net (code "48") (name "Net-(CON2-DETECT)") (class "Default")
      (node (ref "CON2") (pin "19") (pinfunction "DETECT_19") (pintype "bidirectional"))
      (node (ref "R7") (pin "1") (pinfunction "P$1_1") (pintype "passive"))
    )
    (net (code "49") (name "Net-(CON3-LED-A)") (class "Default")
      (node (ref "CON3") (pin "2") (pinfunction "LED-A_2") (pintype "bidirectional"))
      (node (ref "T2") (pin "2") (pinfunction "S_2") (pintype "passive"))
    )
    (net (code "50") (name "Net-(IC3-GND)") (class "Default")
      (node (ref "IC3") (pin "1") (pinfunction "GND_1") (pintype "input"))
      (node (ref "R13") (pin "1") (pinfunction "P$1_1") (pintype "passive"))
      (node (ref "R14") (pin "1") (pinfunction "P$1_1") (pintype "passive"))
    )
    (net (code "51") (name "Net-(IC5-DE)") (class "Default")
      (node (ref "IC5") (pin "46") (pinfunction "DE_46") (pintype "bidirectional"))
      (node (ref "R2") (pin "3M") (pinfunction "3M_3M") (pintype "bidirectional"))
    )
    (net (code "52") (name "Net-(IC5-HSYNC)") (class "Default")
      (node (ref "IC5") (pin "48") (pinfunction "HSYNC_48") (pintype "bidirectional"))
      (node (ref "R2") (pin "1M") (pinfunction "1M_1M") (pintype "bidirectional"))
    )
    (net (code "53") (name "Net-(IC5-ODCK)") (class "Default")
      (node (ref "IC5") (pin "44") (pinfunction "ODCK_44") (pintype "bidirectional"))
      (node (ref "R2") (pin "4M") (pinfunction "4M_4M") (pintype "bidirectional"))
    )
    (net (code "54") (name "Net-(IC5-QE0)") (class "Default")
      (node (ref "IC5") (pin "10") (pinfunction "QE0_10") (pintype "bidirectional"))
      (node (ref "R3") (pin "4M") (pinfunction "4M_4M") (pintype "bidirectional"))
    )
    (net (code "55") (name "Net-(IC5-QE1)") (class "Default")
      (node (ref "IC5") (pin "11") (pinfunction "QE1_11") (pintype "bidirectional"))
      (node (ref "R3") (pin "3M") (pinfunction "3M_3M") (pintype "bidirectional"))
    )
    (net (code "56") (name "Net-(IC5-QE2)") (class "Default")
      (node (ref "IC5") (pin "12") (pinfunction "QE2_12") (pintype "bidirectional"))
      (node (ref "R3") (pin "2M") (pinfunction "2M_2M") (pintype "bidirectional"))
    )
    (net (code "57") (name "Net-(IC5-QE3)") (class "Default")
      (node (ref "IC5") (pin "13") (pinfunction "QE3_13") (pintype "bidirectional"))
      (node (ref "R3") (pin "1M") (pinfunction "1M_1M") (pintype "bidirectional"))
    )
    (net (code "58") (name "Net-(IC5-QE4)") (class "Default")
      (node (ref "IC5") (pin "14") (pinfunction "QE4_14") (pintype "bidirectional"))
      (node (ref "R8") (pin "4M") (pinfunction "4M_4M") (pintype "bidirectional"))
    )
    (net (code "59") (name "Net-(IC5-QE5)") (class "Default")
      (node (ref "IC5") (pin "15") (pinfunction "QE5_15") (pintype "bidirectional"))
      (node (ref "R8") (pin "3M") (pinfunction "3M_3M") (pintype "bidirectional"))
    )
    (net (code "60") (name "Net-(IC5-QE6)") (class "Default")
      (node (ref "IC5") (pin "16") (pinfunction "QE6_16") (pintype "bidirectional"))
      (node (ref "R8") (pin "2M") (pinfunction "2M_2M") (pintype "bidirectional"))
    )
    (net (code "61") (name "Net-(IC5-QE7)") (class "Default")
      (node (ref "IC5") (pin "17") (pinfunction "QE7_17") (pintype "bidirectional"))
      (node (ref "R8") (pin "1M") (pinfunction "1M_1M") (pintype "bidirectional"))
    )
    (net (code "62") (name "Net-(IC5-QE8)") (class "Default")
      (node (ref "IC5") (pin "20") (pinfunction "QE8_20") (pintype "bidirectional"))
      (node (ref "R9") (pin "4M") (pinfunction "4M_4M") (pintype "bidirectional"))
    )
    (net (code "63") (name "Net-(IC5-QE9)") (class "Default")
      (node (ref "IC5") (pin "21") (pinfunction "QE9_21") (pintype "bidirectional"))
      (node (ref "R9") (pin "3M") (pinfunction "3M_3M") (pintype "bidirectional"))
    )
    (net (code "64") (name "Net-(IC5-QE10)") (class "Default")
      (node (ref "IC5") (pin "22") (pinfunction "QE10_22") (pintype "bidirectional"))
      (node (ref "R9") (pin "2M") (pinfunction "2M_2M") (pintype "bidirectional"))
    )
    (net (code "65") (name "Net-(IC5-QE11)") (class "Default")
      (node (ref "IC5") (pin "23") (pinfunction "QE11_23") (pintype "bidirectional"))
      (node (ref "R9") (pin "1M") (pinfunction "1M_1M") (pintype "bidirectional"))
    )
    (net (code "66") (name "Net-(IC5-QE12)") (class "Default")
      (node (ref "IC5") (pin "24") (pinfunction "QE12_24") (pintype "bidirectional"))
      (node (ref "R10") (pin "4M") (pinfunction "4M_4M") (pintype "bidirectional"))
    )
    (net (code "67") (name "Net-(IC5-QE13)") (class "Default")
      (node (ref "IC5") (pin "25") (pinfunction "QE13_25") (pintype "bidirectional"))
      (node (ref "R10") (pin "3M") (pinfunction "3M_3M") (pintype "bidirectional"))
    )
    (net (code "68") (name "Net-(IC5-QE14)") (class "Default")
      (node (ref "IC5") (pin "26") (pinfunction "QE14_26") (pintype "bidirectional"))
      (node (ref "R10") (pin "2M") (pinfunction "2M_2M") (pintype "bidirectional"))
    )
    (net (code "69") (name "Net-(IC5-QE15)") (class "Default")
      (node (ref "IC5") (pin "27") (pinfunction "QE15_27") (pintype "bidirectional"))
      (node (ref "R10") (pin "1M") (pinfunction "1M_1M") (pintype "bidirectional"))
    )
    (net (code "70") (name "Net-(IC5-QE16)") (class "Default")
      (node (ref "IC5") (pin "30") (pinfunction "QE16_30") (pintype "bidirectional"))
      (node (ref "R11") (pin "4M") (pinfunction "4M_4M") (pintype "bidirectional"))
    )
    (net (code "71") (name "Net-(IC5-QE17)") (class "Default")
      (node (ref "IC5") (pin "31") (pinfunction "QE17_31") (pintype "bidirectional"))
      (node (ref "R11") (pin "3M") (pinfunction "3M_3M") (pintype "bidirectional"))
    )
    (net (code "72") (name "Net-(IC5-QE18)") (class "Default")
      (node (ref "IC5") (pin "32") (pinfunction "QE18_32") (pintype "bidirectional"))
      (node (ref "R11") (pin "2M") (pinfunction "2M_2M") (pintype "bidirectional"))
    )
    (net (code "73") (name "Net-(IC5-QE19)") (class "Default")
      (node (ref "IC5") (pin "33") (pinfunction "QE19_33") (pintype "bidirectional"))
      (node (ref "R11") (pin "1M") (pinfunction "1M_1M") (pintype "bidirectional"))
    )
    (net (code "74") (name "Net-(IC5-QE20)") (class "Default")
      (node (ref "IC5") (pin "34") (pinfunction "QE20_34") (pintype "bidirectional"))
      (node (ref "R12") (pin "4M") (pinfunction "4M_4M") (pintype "bidirectional"))
    )
    (net (code "75") (name "Net-(IC5-QE21)") (class "Default")
      (node (ref "IC5") (pin "35") (pinfunction "QE21_35") (pintype "bidirectional"))
      (node (ref "R12") (pin "3M") (pinfunction "3M_3M") (pintype "bidirectional"))
    )
    (net (code "76") (name "Net-(IC5-QE22)") (class "Default")
      (node (ref "IC5") (pin "36") (pinfunction "QE22_36") (pintype "bidirectional"))
      (node (ref "R12") (pin "2M") (pinfunction "2M_2M") (pintype "bidirectional"))
    )
    (net (code "77") (name "Net-(IC5-QE23)") (class "Default")
      (node (ref "IC5") (pin "37") (pinfunction "QE23_37") (pintype "bidirectional"))
      (node (ref "R12") (pin "1M") (pinfunction "1M_1M") (pintype "bidirectional"))
    )
    (net (code "78") (name "Net-(IC5-VSYNC)") (class "Default")
      (node (ref "IC5") (pin "47") (pinfunction "VSYNC_47") (pintype "bidirectional"))
      (node (ref "R2") (pin "2M") (pinfunction "2M_2M") (pintype "bidirectional"))
    )
    (net (code "79") (name "Net-(IC7-USBDM)") (class "Default")
      (node (ref "IC7") (pin "16") (pinfunction "USBDM_16") (pintype "bidirectional"))
      (node (ref "R23") (pin "2") (pinfunction "P$2_2") (pintype "passive"))
    )
    (net (code "80") (name "Net-(IC7-USBDP)") (class "Default")
      (node (ref "IC7") (pin "15") (pinfunction "USBDP_15") (pintype "bidirectional"))
      (node (ref "R22") (pin "2") (pinfunction "P$2_2") (pintype "passive"))
    )
    (net (code "81") (name "Net-(R1-P$2)") (class "Default")
      (node (ref "D1") (pin "A") (pinfunction "A_A") (pintype "passive"))
      (node (ref "R1") (pin "2") (pinfunction "P$2_2") (pintype "passive"))
      (node (ref "T1") (pin "1") (pinfunction "G_1") (pintype "passive"))
    )
    (net (code "82") (name "Net-(R20-P$1)") (class "Default")
      (node (ref "R20") (pin "1") (pinfunction "P$1_1") (pintype "passive"))
      (node (ref "R21") (pin "1") (pinfunction "P$1_1") (pintype "passive"))
      (node (ref "T2") (pin "3") (pinfunction "D_3") (pintype "passive"))
    )
    (net (code "83") (name "RGB_DE") (class "Default")
      (node (ref "CON3") (pin "34") (pinfunction "DEN_34") (pintype "bidirectional"))
      (node (ref "IC8") (pin "30") (pinfunction "D26_30") (pintype "bidirectional"))
      (node (ref "R2") (pin "3P") (pinfunction "3P_3P") (pintype "bidirectional"))
    )
    (net (code "84") (name "RGB_DISP") (class "Default")
      (node (ref "CON3") (pin "31") (pinfunction "DISP_31") (pintype "bidirectional"))
      (node (ref "JP3") (pin "2") (pinfunction "2_2") (pintype "passive"))
      (node (ref "R15") (pin "1") (pinfunction "P$1_1") (pintype "passive"))
    )
    (net (code "85") (name "RGB_EVEN_B0") (class "Default")
      (node (ref "CON3") (pin "21") (pinfunction "B0_21") (pintype "bidirectional"))
      (node (ref "IC8") (pin "15") (pinfunction "D15_15") (pintype "bidirectional"))
      (node (ref "R3") (pin "4P") (pinfunction "4P_4P") (pintype "bidirectional"))
    )
    (net (code "86") (name "RGB_EVEN_B1") (class "Default")
      (node (ref "CON3") (pin "22") (pinfunction "B1_22") (pintype "bidirectional"))
      (node (ref "IC8") (pin "19") (pinfunction "D18_19") (pintype "bidirectional"))
      (node (ref "R3") (pin "3P") (pinfunction "3P_3P") (pintype "bidirectional"))
    )
    (net (code "87") (name "RGB_EVEN_B2") (class "Default")
      (node (ref "CON3") (pin "23") (pinfunction "B2_23") (pintype "bidirectional"))
      (node (ref "IC8") (pin "20") (pinfunction "D19_20") (pintype "bidirectional"))
      (node (ref "R3") (pin "2P") (pinfunction "2P_2P") (pintype "bidirectional"))
    )
    (net (code "88") (name "RGB_EVEN_B3") (class "Default")
      (node (ref "CON3") (pin "24") (pinfunction "B3_24") (pintype "bidirectional"))
      (node (ref "IC8") (pin "22") (pinfunction "D20_22") (pintype "bidirectional"))
      (node (ref "R3") (pin "1P") (pinfunction "1P_1P") (pintype "bidirectional"))
    )
    (net (code "89") (name "RGB_EVEN_B4") (class "Default")
      (node (ref "CON3") (pin "25") (pinfunction "B4_25") (pintype "bidirectional"))
      (node (ref "IC8") (pin "23") (pinfunction "D21_23") (pintype "bidirectional"))
      (node (ref "R8") (pin "4P") (pinfunction "4P_4P") (pintype "bidirectional"))
    )
    (net (code "90") (name "RGB_EVEN_B5") (class "Default")
      (node (ref "CON3") (pin "26") (pinfunction "B5_26") (pintype "bidirectional"))
      (node (ref "IC8") (pin "24") (pinfunction "D22_24") (pintype "bidirectional"))
      (node (ref "R8") (pin "3P") (pinfunction "3P_3P") (pintype "bidirectional"))
    )
    (net (code "91") (name "RGB_EVEN_B6") (class "Default")
      (node (ref "CON3") (pin "27") (pinfunction "B6_27") (pintype "bidirectional"))
      (node (ref "IC8") (pin "16") (pinfunction "D16_16") (pintype "bidirectional"))
      (node (ref "R8") (pin "2P") (pinfunction "2P_2P") (pintype "bidirectional"))
    )
    (net (code "92") (name "RGB_EVEN_B7") (class "Default")
      (node (ref "CON3") (pin "28") (pinfunction "B7_28") (pintype "bidirectional"))
      (node (ref "IC8") (pin "18") (pinfunction "D17_18") (pintype "bidirectional"))
      (node (ref "R8") (pin "1P") (pinfunction "1P_1P") (pintype "bidirectional"))
    )
    (net (code "93") (name "RGB_EVEN_G0") (class "Default")
      (node (ref "CON3") (pin "13") (pinfunction "G0_13") (pintype "bidirectional"))
      (node (ref "IC8") (pin "4") (pinfunction "D7_4") (pintype "bidirectional"))
      (node (ref "R9") (pin "4P") (pinfunction "4P_4P") (pintype "bidirectional"))
    )
    (net (code "94") (name "RGB_EVEN_G1") (class "Default")
      (node (ref "CON3") (pin "14") (pinfunction "G1_14") (pintype "bidirectional"))
      (node (ref "IC8") (pin "6") (pinfunction "D8_6") (pintype "bidirectional"))
      (node (ref "R9") (pin "3P") (pinfunction "3P_3P") (pintype "bidirectional"))
    )
    (net (code "95") (name "RGB_EVEN_G2") (class "Default")
      (node (ref "CON3") (pin "15") (pinfunction "G2_15") (pintype "bidirectional"))
      (node (ref "IC8") (pin "7") (pinfunction "D9_7") (pintype "bidirectional"))
      (node (ref "R9") (pin "2P") (pinfunction "2P_2P") (pintype "bidirectional"))
    )
    (net (code "96") (name "RGB_EVEN_G3") (class "Default")
      (node (ref "CON3") (pin "16") (pinfunction "G3_16") (pintype "bidirectional"))
      (node (ref "IC8") (pin "11") (pinfunction "D12_11") (pintype "bidirectional"))
      (node (ref "R9") (pin "1P") (pinfunction "1P_1P") (pintype "bidirectional"))
    )
    (net (code "97") (name "RGB_EVEN_G4") (class "Default")
      (node (ref "CON3") (pin "17") (pinfunction "G4_17") (pintype "bidirectional"))
      (node (ref "IC8") (pin "12") (pinfunction "D13_12") (pintype "bidirectional"))
      (node (ref "R10") (pin "4P") (pinfunction "4P_4P") (pintype "bidirectional"))
    )
    (net (code "98") (name "RGB_EVEN_G5") (class "Default")
      (node (ref "CON3") (pin "18") (pinfunction "G5_18") (pintype "bidirectional"))
      (node (ref "IC8") (pin "14") (pinfunction "D14_14") (pintype "bidirectional"))
      (node (ref "R10") (pin "3P") (pinfunction "3P_3P") (pintype "bidirectional"))
    )
    (net (code "99") (name "RGB_EVEN_G6") (class "Default")
      (node (ref "CON3") (pin "19") (pinfunction "G6_19") (pintype "bidirectional"))
      (node (ref "IC8") (pin "8") (pinfunction "D10_8") (pintype "bidirectional"))
      (node (ref "R10") (pin "2P") (pinfunction "2P_2P") (pintype "bidirectional"))
    )
    (net (code "100") (name "RGB_EVEN_G7") (class "Default")
      (node (ref "CON3") (pin "20") (pinfunction "G7_20") (pintype "bidirectional"))
      (node (ref "IC8") (pin "10") (pinfunction "D11_10") (pintype "bidirectional"))
      (node (ref "R10") (pin "1P") (pinfunction "1P_1P") (pintype "bidirectional"))
    )
    (net (code "101") (name "RGB_EVEN_R0") (class "Default")
      (node (ref "CON3") (pin "5") (pinfunction "R0_5") (pintype "bidirectional"))
      (node (ref "IC8") (pin "51") (pinfunction "D0_51") (pintype "bidirectional"))
      (node (ref "R11") (pin "4P") (pinfunction "4P_4P") (pintype "bidirectional"))
    )
    (net (code "102") (name "RGB_EVEN_R1") (class "Default")
      (node (ref "CON3") (pin "6") (pinfunction "R1_6") (pintype "bidirectional"))
      (node (ref "IC8") (pin "52") (pinfunction "D1_52") (pintype "bidirectional"))
      (node (ref "R11") (pin "3P") (pinfunction "3P_3P") (pintype "bidirectional"))
    )
    (net (code "103") (name "RGB_EVEN_R2") (class "Default")
      (node (ref "CON3") (pin "7") (pinfunction "R2_7") (pintype "bidirectional"))
      (node (ref "IC8") (pin "54") (pinfunction "D2_54") (pintype "bidirectional"))
      (node (ref "R11") (pin "2P") (pinfunction "2P_2P") (pintype "bidirectional"))
    )
    (net (code "104") (name "RGB_EVEN_R3") (class "Default")
      (node (ref "CON3") (pin "8") (pinfunction "R3_8") (pintype "bidirectional"))
      (node (ref "IC8") (pin "55") (pinfunction "D3_55") (pintype "bidirectional"))
      (node (ref "R11") (pin "1P") (pinfunction "1P_1P") (pintype "bidirectional"))
    )
    (net (code "105") (name "RGB_EVEN_R4") (class "Default")
      (node (ref "CON3") (pin "9") (pinfunction "R4_9") (pintype "bidirectional"))
      (node (ref "IC8") (pin "56") (pinfunction "D4_56") (pintype "bidirectional"))
      (node (ref "R12") (pin "4P") (pinfunction "4P_4P") (pintype "bidirectional"))
    )
    (net (code "106") (name "RGB_EVEN_R5") (class "Default")
      (node (ref "CON3") (pin "10") (pinfunction "R5_10") (pintype "bidirectional"))
      (node (ref "IC8") (pin "3") (pinfunction "D6_3") (pintype "bidirectional"))
      (node (ref "R12") (pin "3P") (pinfunction "3P_3P") (pintype "bidirectional"))
    )
    (net (code "107") (name "RGB_EVEN_R6") (class "Default")
      (node (ref "CON3") (pin "11") (pinfunction "R6_11") (pintype "bidirectional"))
      (node (ref "IC8") (pin "50") (pinfunction "D27_50") (pintype "bidirectional"))
      (node (ref "R12") (pin "2P") (pinfunction "2P_2P") (pintype "bidirectional"))
    )
    (net (code "108") (name "RGB_EVEN_R7") (class "Default")
      (node (ref "CON3") (pin "12") (pinfunction "R7_12") (pintype "bidirectional"))
      (node (ref "IC8") (pin "2") (pinfunction "D5_2") (pintype "bidirectional"))
      (node (ref "R12") (pin "1P") (pinfunction "1P_1P") (pintype "bidirectional"))
    )
    (net (code "109") (name "RGB_HSYNC") (class "Default")
      (node (ref "CON3") (pin "32") (pinfunction "HSYNC_32") (pintype "bidirectional"))
      (node (ref "IC8") (pin "27") (pinfunction "D24_27") (pintype "bidirectional"))
      (node (ref "R2") (pin "2P") (pinfunction "2P_2P") (pintype "bidirectional"))
    )
    (net (code "110") (name "RGB_ODCK") (class "Default")
      (node (ref "CON3") (pin "30") (pinfunction "CLK_30") (pintype "bidirectional"))
      (node (ref "IC8") (pin "31") (pinfunction "CLKIN_31") (pintype "bidirectional"))
      (node (ref "R2") (pin "4P") (pinfunction "4P_4P") (pintype "bidirectional"))
    )
    (net (code "111") (name "RGB_PWM") (class "Default")
      (node (ref "JP4") (pin "3") (pinfunction "3_3") (pintype "passive"))
      (node (ref "JP6") (pin "1") (pinfunction "1_1") (pintype "passive"))
    )
    (net (code "112") (name "RGB_PWM_EN") (class "Default")
      (node (ref "JP4") (pin "2") (pinfunction "2_2") (pintype "passive"))
      (node (ref "T2") (pin "1") (pinfunction "G_1") (pintype "passive"))
    )
    (net (code "113") (name "RGB_VSYNC") (class "Default")
      (node (ref "CON3") (pin "33") (pinfunction "VSYNC_33") (pintype "bidirectional"))
      (node (ref "IC8") (pin "28") (pinfunction "D25_28") (pintype "bidirectional"))
      (node (ref "R2") (pin "1P") (pinfunction "1P_1P") (pintype "bidirectional"))
    )
    (net (code "114") (name "USB_D+") (class "Default")
      (node (ref "CON4") (pin "3") (pinfunction "D+_3") (pintype "bidirectional"))
      (node (ref "R23") (pin "1") (pinfunction "P$1_1") (pintype "passive"))
    )
    (net (code "115") (name "USB_D-") (class "Default")
      (node (ref "CON4") (pin "2") (pinfunction "D-_2") (pintype "bidirectional"))
      (node (ref "R22") (pin "1") (pinfunction "P$1_1") (pintype "passive"))
    )
    (net (code "116") (name "unconnected-(CON2-CEC-Pad13)") (class "Default")
      (node (ref "CON2") (pin "13") (pinfunction "CEC_13") (pintype "bidirectional"))
    )
    (net (code "117") (name "unconnected-(CON2-NC-Pad14)") (class "Default")
      (node (ref "CON2") (pin "14") (pinfunction "NC_14") (pintype "bidirectional"))
    )
    (net (code "118") (name "unconnected-(CON3-NC-Pad35)") (class "Default")
      (node (ref "CON3") (pin "35") (pinfunction "NC_35") (pintype "bidirectional"))
    )
    (net (code "119") (name "unconnected-(CON3-XL-Pad39)") (class "Default")
      (node (ref "CON3") (pin "39") (pinfunction "XL_39") (pintype "bidirectional"))
    )
    (net (code "120") (name "unconnected-(CON3-XR-Pad37)") (class "Default")
      (node (ref "CON3") (pin "37") (pinfunction "XR_37") (pintype "bidirectional"))
    )
    (net (code "121") (name "unconnected-(CON3-YD-Pad38)") (class "Default")
      (node (ref "CON3") (pin "38") (pinfunction "YD_38") (pintype "bidirectional"))
    )
    (net (code "122") (name "unconnected-(CON3-YU-Pad40)") (class "Default")
      (node (ref "CON3") (pin "40") (pinfunction "YU_40") (pintype "bidirectional"))
    )
    (net (code "123") (name "unconnected-(CON4-ID-Pad4)") (class "Default")
      (node (ref "CON4") (pin "4") (pinfunction "ID_4") (pintype "bidirectional"))
    )
    (net (code "124") (name "unconnected-(CON6-NC-Pad27)") (class "Default")
      (node (ref "CON6") (pin "27") (pinfunction "NC_27") (pintype "bidirectional"))
    )
    (net (code "125") (name "unconnected-(CON6-TP-Pad22)") (class "Default")
      (node (ref "CON6") (pin "22") (pinfunction "TP_22") (pintype "bidirectional"))
    )
    (net (code "126") (name "unconnected-(CON6-TP-Pad23)") (class "Default")
      (node (ref "CON6") (pin "23") (pinfunction "TP_23") (pintype "bidirectional"))
    )
    (net (code "127") (name "unconnected-(IC1-EN-Pad5)") (class "Default")
      (node (ref "IC1") (pin "5") (pinfunction "EN_5") (pintype "bidirectional"))
    )
    (net (code "128") (name "unconnected-(IC1-PG-Pad4)") (class "Default")
      (node (ref "IC1") (pin "4") (pinfunction "PG_4") (pintype "bidirectional"))
    )
    (net (code "129") (name "unconnected-(IC2-EN-Pad5)") (class "Default")
      (node (ref "IC2") (pin "5") (pinfunction "EN_5") (pintype "bidirectional"))
    )
    (net (code "130") (name "unconnected-(IC2-PG-Pad4)") (class "Default")
      (node (ref "IC2") (pin "4") (pinfunction "PG_4") (pintype "bidirectional"))
    )
    (net (code "131") (name "unconnected-(IC5-CTL1-Pad40)") (class "Default")
      (node (ref "IC5") (pin "40") (pinfunction "CTL1_40") (pintype "bidirectional"))
    )
    (net (code "132") (name "unconnected-(IC5-CTL2-Pad41)") (class "Default")
      (node (ref "IC5") (pin "41") (pinfunction "CTL2_41") (pintype "bidirectional"))
    )
    (net (code "133") (name "unconnected-(IC5-CTL3-Pad42)") (class "Default")
      (node (ref "IC5") (pin "42") (pinfunction "CTL3_42") (pintype "bidirectional"))
    )
    (net (code "134") (name "unconnected-(IC5-EXT_RES-Pad96)") (class "Default")
      (node (ref "IC5") (pin "96") (pinfunction "EXT_RES_96") (pintype "bidirectional"))
    )
    (net (code "135") (name "unconnected-(IC5-QO0-Pad49)") (class "Default")
      (node (ref "IC5") (pin "49") (pinfunction "QO0_49") (pintype "bidirectional"))
    )
    (net (code "136") (name "unconnected-(IC5-QO1-Pad50)") (class "Default")
      (node (ref "IC5") (pin "50") (pinfunction "QO1_50") (pintype "bidirectional"))
    )
    (net (code "137") (name "unconnected-(IC5-QO2-Pad51)") (class "Default")
      (node (ref "IC5") (pin "51") (pinfunction "QO2_51") (pintype "bidirectional"))
    )
    (net (code "138") (name "unconnected-(IC5-QO3-Pad52)") (class "Default")
      (node (ref "IC5") (pin "52") (pinfunction "QO3_52") (pintype "bidirectional"))
    )
    (net (code "139") (name "unconnected-(IC5-QO4-Pad53)") (class "Default")
      (node (ref "IC5") (pin "53") (pinfunction "QO4_53") (pintype "bidirectional"))
    )
    (net (code "140") (name "unconnected-(IC5-QO5-Pad54)") (class "Default")
      (node (ref "IC5") (pin "54") (pinfunction "QO5_54") (pintype "bidirectional"))
    )
    (net (code "141") (name "unconnected-(IC5-QO6-Pad55)") (class "Default")
      (node (ref "IC5") (pin "55") (pinfunction "QO6_55") (pintype "bidirectional"))
    )
    (net (code "142") (name "unconnected-(IC5-QO7-Pad56)") (class "Default")
      (node (ref "IC5") (pin "56") (pinfunction "QO7_56") (pintype "bidirectional"))
    )
    (net (code "143") (name "unconnected-(IC5-QO8-Pad59)") (class "Default")
      (node (ref "IC5") (pin "59") (pinfunction "QO8_59") (pintype "bidirectional"))
    )
    (net (code "144") (name "unconnected-(IC5-QO9-Pad60)") (class "Default")
      (node (ref "IC5") (pin "60") (pinfunction "QO9_60") (pintype "bidirectional"))
    )
    (net (code "145") (name "unconnected-(IC5-QO10-Pad61)") (class "Default")
      (node (ref "IC5") (pin "61") (pinfunction "QO10_61") (pintype "bidirectional"))
    )
    (net (code "146") (name "unconnected-(IC5-QO11-Pad62)") (class "Default")
      (node (ref "IC5") (pin "62") (pinfunction "QO11_62") (pintype "bidirectional"))
    )
    (net (code "147") (name "unconnected-(IC5-QO12-Pad63)") (class "Default")
      (node (ref "IC5") (pin "63") (pinfunction "QO12_63") (pintype "bidirectional"))
    )
    (net (code "148") (name "unconnected-(IC5-QO13-Pad64)") (class "Default")
      (node (ref "IC5") (pin "64") (pinfunction "QO13_64") (pintype "bidirectional"))
    )
    (net (code "149") (name "unconnected-(IC5-QO14-Pad65)") (class "Default")
      (node (ref "IC5") (pin "65") (pinfunction "QO14_65") (pintype "bidirectional"))
    )
    (net (code "150") (name "unconnected-(IC5-QO15-Pad66)") (class "Default")
      (node (ref "IC5") (pin "66") (pinfunction "QO15_66") (pintype "bidirectional"))
    )
    (net (code "151") (name "unconnected-(IC5-QO16-Pad69)") (class "Default")
      (node (ref "IC5") (pin "69") (pinfunction "QO16_69") (pintype "bidirectional"))
    )
    (net (code "152") (name "unconnected-(IC5-QO17-Pad70)") (class "Default")
      (node (ref "IC5") (pin "70") (pinfunction "QO17_70") (pintype "bidirectional"))
    )
    (net (code "153") (name "unconnected-(IC5-QO18-Pad71)") (class "Default")
      (node (ref "IC5") (pin "71") (pinfunction "QO18_71") (pintype "bidirectional"))
    )
    (net (code "154") (name "unconnected-(IC5-QO19-Pad72)") (class "Default")
      (node (ref "IC5") (pin "72") (pinfunction "QO19_72") (pintype "bidirectional"))
    )
    (net (code "155") (name "unconnected-(IC5-QO20-Pad73)") (class "Default")
      (node (ref "IC5") (pin "73") (pinfunction "QO20_73") (pintype "bidirectional"))
    )
    (net (code "156") (name "unconnected-(IC5-QO21-Pad74)") (class "Default")
      (node (ref "IC5") (pin "74") (pinfunction "QO21_74") (pintype "bidirectional"))
    )
    (net (code "157") (name "unconnected-(IC5-QO22-Pad75)") (class "Default")
      (node (ref "IC5") (pin "75") (pinfunction "QO22_75") (pintype "bidirectional"))
    )
    (net (code "158") (name "unconnected-(IC5-QO23-Pad77)") (class "Default")
      (node (ref "IC5") (pin "77") (pinfunction "QO23_77") (pintype "bidirectional"))
    )
    (net (code "159") (name "unconnected-(IC5-SCDT-Pad8)") (class "Default")
      (node (ref "IC5") (pin "8") (pinfunction "SCDT_8") (pintype "bidirectional"))
    )
    (net (code "160") (name "unconnected-(IC5-~{PDO}-Pad9)") (class "Default")
      (node (ref "IC5") (pin "9") (pinfunction "~{PDO}_9") (pintype "bidirectional"))
    )
    (net (code "161") (name "unconnected-(IC5-~{PD}-Pad2)") (class "Default")
      (node (ref "IC5") (pin "2") (pinfunction "~{PD}_2") (pintype "bidirectional"))
    )
    (net (code "162") (name "unconnected-(IC6-(PCINT18{slash}INT0)PD2-Pad32)") (class "Default")
      (node (ref "IC6") (pin "32") (pinfunction "(PCINT18/INT0)PD2_32") (pintype "bidirectional"))
    )
    (net (code "163") (name "unconnected-(IC6-(PCINT19{slash}OC2B{slash}INT1)PD3-Pad1)") (class "Default")
      (node (ref "IC6") (pin "1") (pinfunction "(PCINT19/OC2B/INT1)PD3_1") (pintype "bidirectional"))
    )
    (net (code "164") (name "unconnected-(IC6-(PCINT20{slash}XCK{slash}T0)PD4-Pad2)") (class "Default")
      (node (ref "IC6") (pin "2") (pinfunction "(PCINT20/XCK/T0)PD4_2") (pintype "bidirectional"))
    )
    (net (code "165") (name "unconnected-(IC6-(PCINT21{slash}OC0B{slash}T1)PD5-Pad9)") (class "Default")
      (node (ref "IC6") (pin "9") (pinfunction "(PCINT21/OC0B/T1)PD5_9") (pintype "bidirectional"))
    )
    (net (code "166") (name "unconnected-(IC6-(PCINT22{slash}OC0A{slash}AIN0)PD6-Pad10)") (class "Default")
      (node (ref "IC6") (pin "10") (pinfunction "(PCINT22/OC0A/AIN0)PD6_10") (pintype "bidirectional"))
    )
    (net (code "167") (name "unconnected-(IC6-(PCINT23{slash}AIN1)PD7-Pad11)") (class "Default")
      (node (ref "IC6") (pin "11") (pinfunction "(PCINT23/AIN1)PD7_11") (pintype "bidirectional"))
    )
    (net (code "168") (name "unconnected-(IC6-ADC6-Pad19)") (class "Default")
      (node (ref "IC6") (pin "19") (pinfunction "ADC6_19") (pintype "bidirectional"))
    )
    (net (code "169") (name "unconnected-(IC6-ADC7-Pad22)") (class "Default")
      (node (ref "IC6") (pin "22") (pinfunction "ADC7_22") (pintype "bidirectional"))
    )
    (net (code "170") (name "unconnected-(IC6-PB0(PCINT0{slash}CLKO{slash}ICP1)-Pad12)") (class "Default")
      (node (ref "IC6") (pin "12") (pinfunction "PB0(PCINT0/CLKO/ICP1)_12") (pintype "bidirectional"))
    )
    (net (code "171") (name "unconnected-(IC6-PB2(SS{slash}OC1B{slash}PCINT2)-Pad14)") (class "Default")
      (node (ref "IC6") (pin "14") (pinfunction "PB2(SS/OC1B/PCINT2)_14") (pintype "bidirectional"))
    )
    (net (code "172") (name "unconnected-(IC6-PC1(ADC1{slash}PCINT9)-Pad24)") (class "Default")
      (node (ref "IC6") (pin "24") (pinfunction "PC1(ADC1/PCINT9)_24") (pintype "bidirectional"))
    )
    (net (code "173") (name "unconnected-(IC6-PC2(ADC2{slash}PCINT10)-Pad25)") (class "Default")
      (node (ref "IC6") (pin "25") (pinfunction "PC2(ADC2/PCINT10)_25") (pintype "bidirectional"))
    )
    (net (code "174") (name "unconnected-(IC6-PC3(ADC3{slash}PCINT11)-Pad26)") (class "Default")
      (node (ref "IC6") (pin "26") (pinfunction "PC3(ADC3/PCINT11)_26") (pintype "bidirectional"))
    )
    (net (code "175") (name "unconnected-(IC7-CBUS0-Pad23)") (class "Default")
      (node (ref "IC7") (pin "23") (pinfunction "CBUS0_23") (pintype "bidirectional"))
    )
    (net (code "176") (name "unconnected-(IC7-CBUS1-Pad22)") (class "Default")
      (node (ref "IC7") (pin "22") (pinfunction "CBUS1_22") (pintype "bidirectional"))
    )
    (net (code "177") (name "unconnected-(IC7-CBUS2-Pad13)") (class "Default")
      (node (ref "IC7") (pin "13") (pinfunction "CBUS2_13") (pintype "bidirectional"))
    )
    (net (code "178") (name "unconnected-(IC7-CBUS3-Pad14)") (class "Default")
      (node (ref "IC7") (pin "14") (pinfunction "CBUS3_14") (pintype "bidirectional"))
    )
    (net (code "179") (name "unconnected-(IC7-CBUS4-Pad12)") (class "Default")
      (node (ref "IC7") (pin "12") (pinfunction "CBUS4_12") (pintype "bidirectional"))
    )
    (net (code "180") (name "unconnected-(IC7-OSCI-Pad27)") (class "Default")
      (node (ref "IC7") (pin "27") (pinfunction "OSCI_27") (pintype "input"))
    )
    (net (code "181") (name "unconnected-(IC7-OSCO-Pad28)") (class "Default")
      (node (ref "IC7") (pin "28") (pinfunction "OSCO_28") (pintype "output"))
    )
    (net (code "182") (name "unconnected-(IC7-~{CTS}-Pad11)") (class "Default")
      (node (ref "IC7") (pin "11") (pinfunction "~{CTS}_11") (pintype "input"))
    )
    (net (code "183") (name "unconnected-(IC7-~{DCD}-Pad10)") (class "Default")
      (node (ref "IC7") (pin "10") (pinfunction "~{DCD}_10") (pintype "input"))
    )
    (net (code "184") (name "unconnected-(IC7-~{DSR}-Pad9)") (class "Default")
      (node (ref "IC7") (pin "9") (pinfunction "~{DSR}_9") (pintype "input"))
    )
    (net (code "185") (name "unconnected-(IC7-~{DTR}-Pad2)") (class "Default")
      (node (ref "IC7") (pin "2") (pinfunction "~{DTR}_2") (pintype "output"))
    )
    (net (code "186") (name "unconnected-(IC7-~{RI}-Pad6)") (class "Default")
      (node (ref "IC7") (pin "6") (pinfunction "~{RI}_6") (pintype "input"))
    )
    (net (code "187") (name "unconnected-(IC7-~{RTS}-Pad3)") (class "Default")
      (node (ref "IC7") (pin "3") (pinfunction "~{RTS}_3") (pintype "output"))
    )
    (net (code "188") (name "unconnected-(IC8-CLKSEL-Pad17)") (class "Default")
      (node (ref "IC8") (pin "17") (pinfunction "CLKSEL_17") (pintype "bidirectional"))
    )
    (net (code "189") (name "unconnected-(IC8-~{SHTDN}-Pad32)") (class "Default")
      (node (ref "IC8") (pin "32") (pinfunction "~{SHTDN}_32") (pintype "bidirectional"))
    )
  )
)
